# EEG_cap_v3.net
KiCad netlist of a schematic drawn in EAGLE
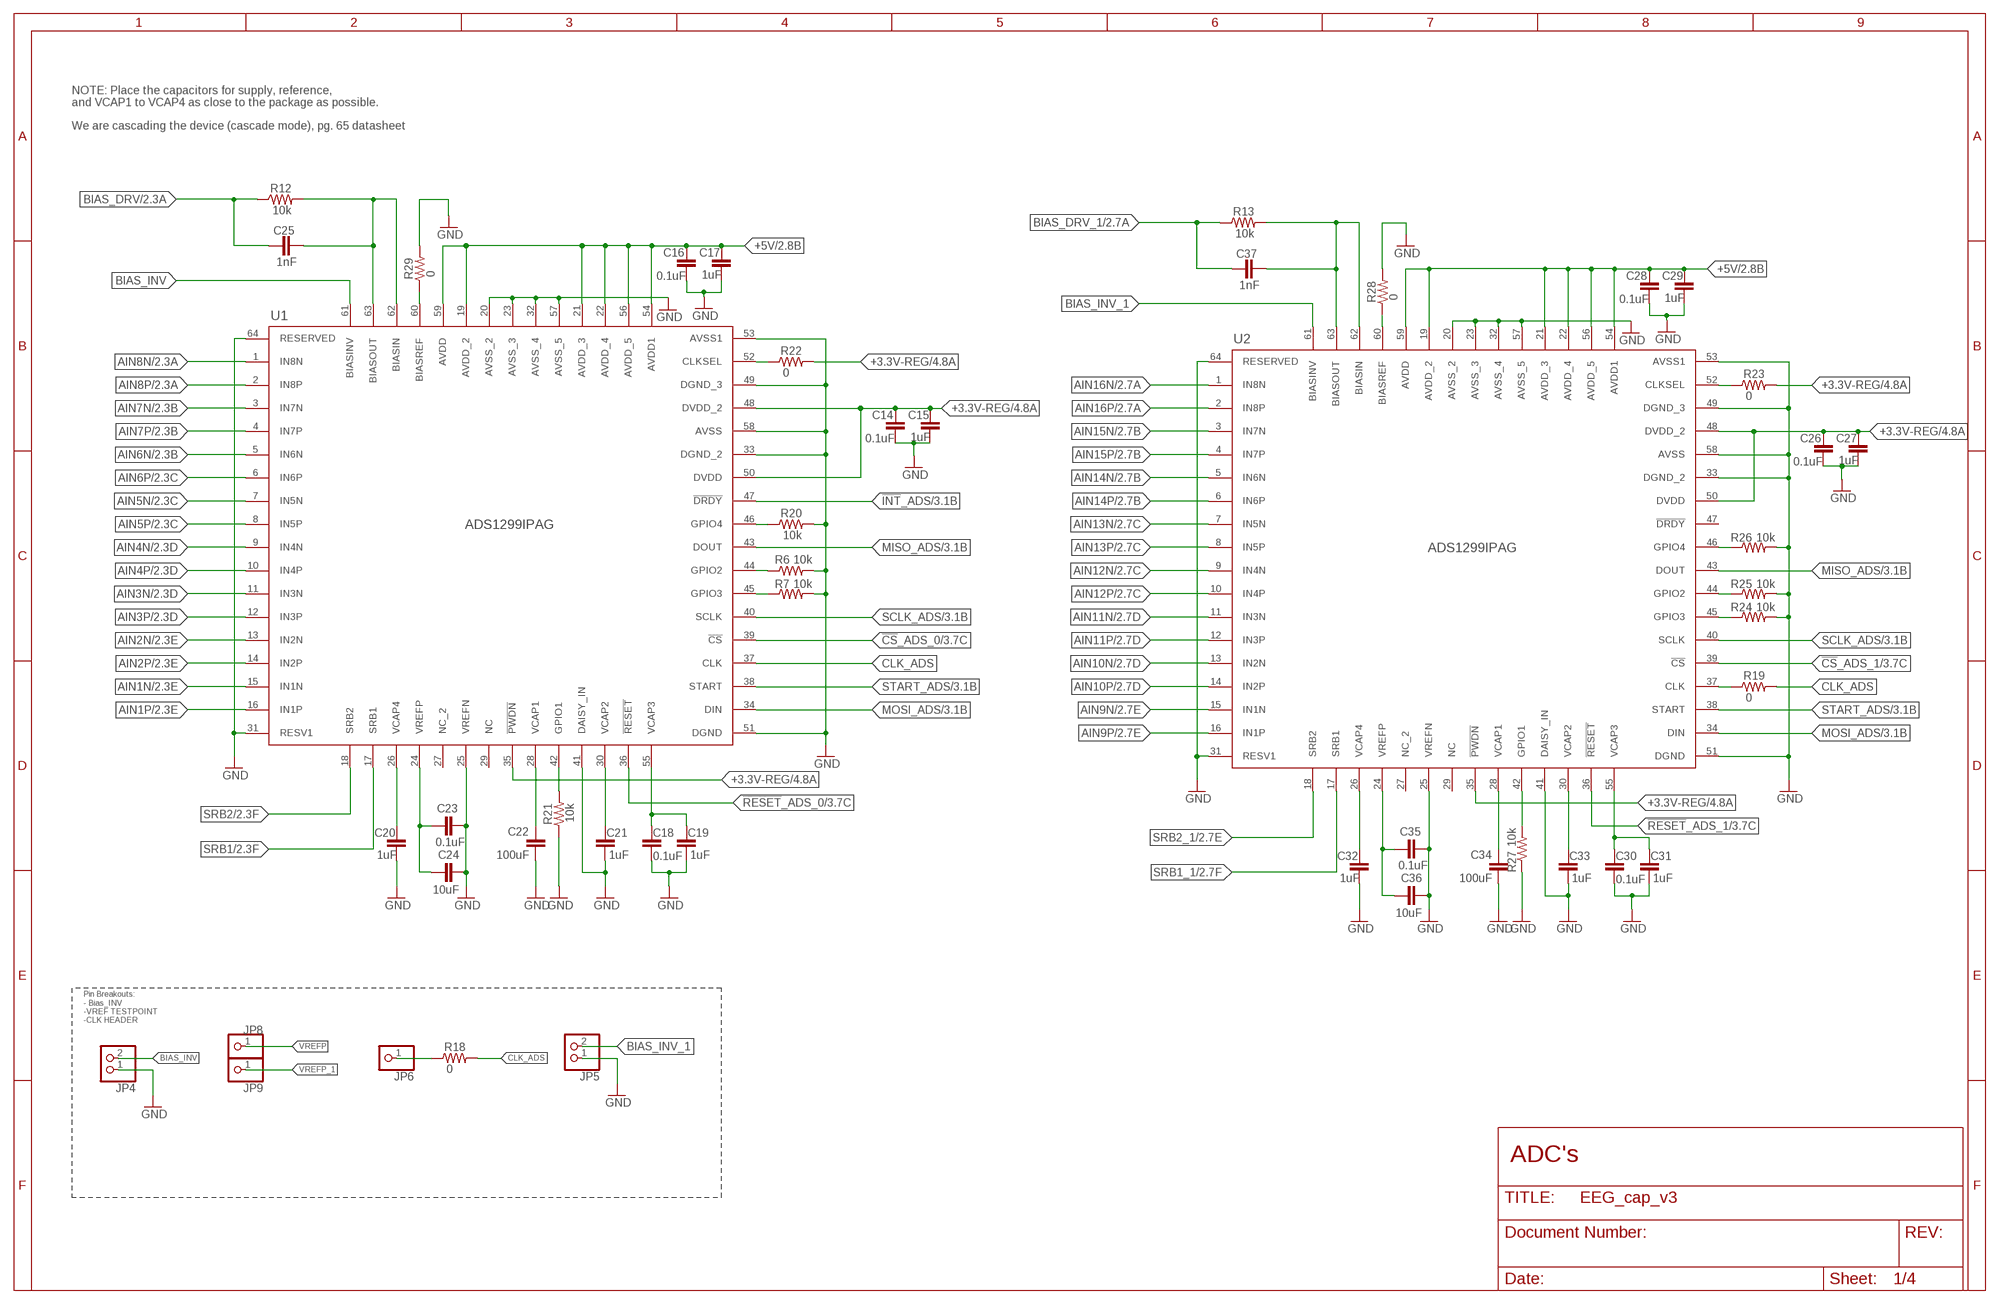
[diagram p0: schematic, sheet 1]
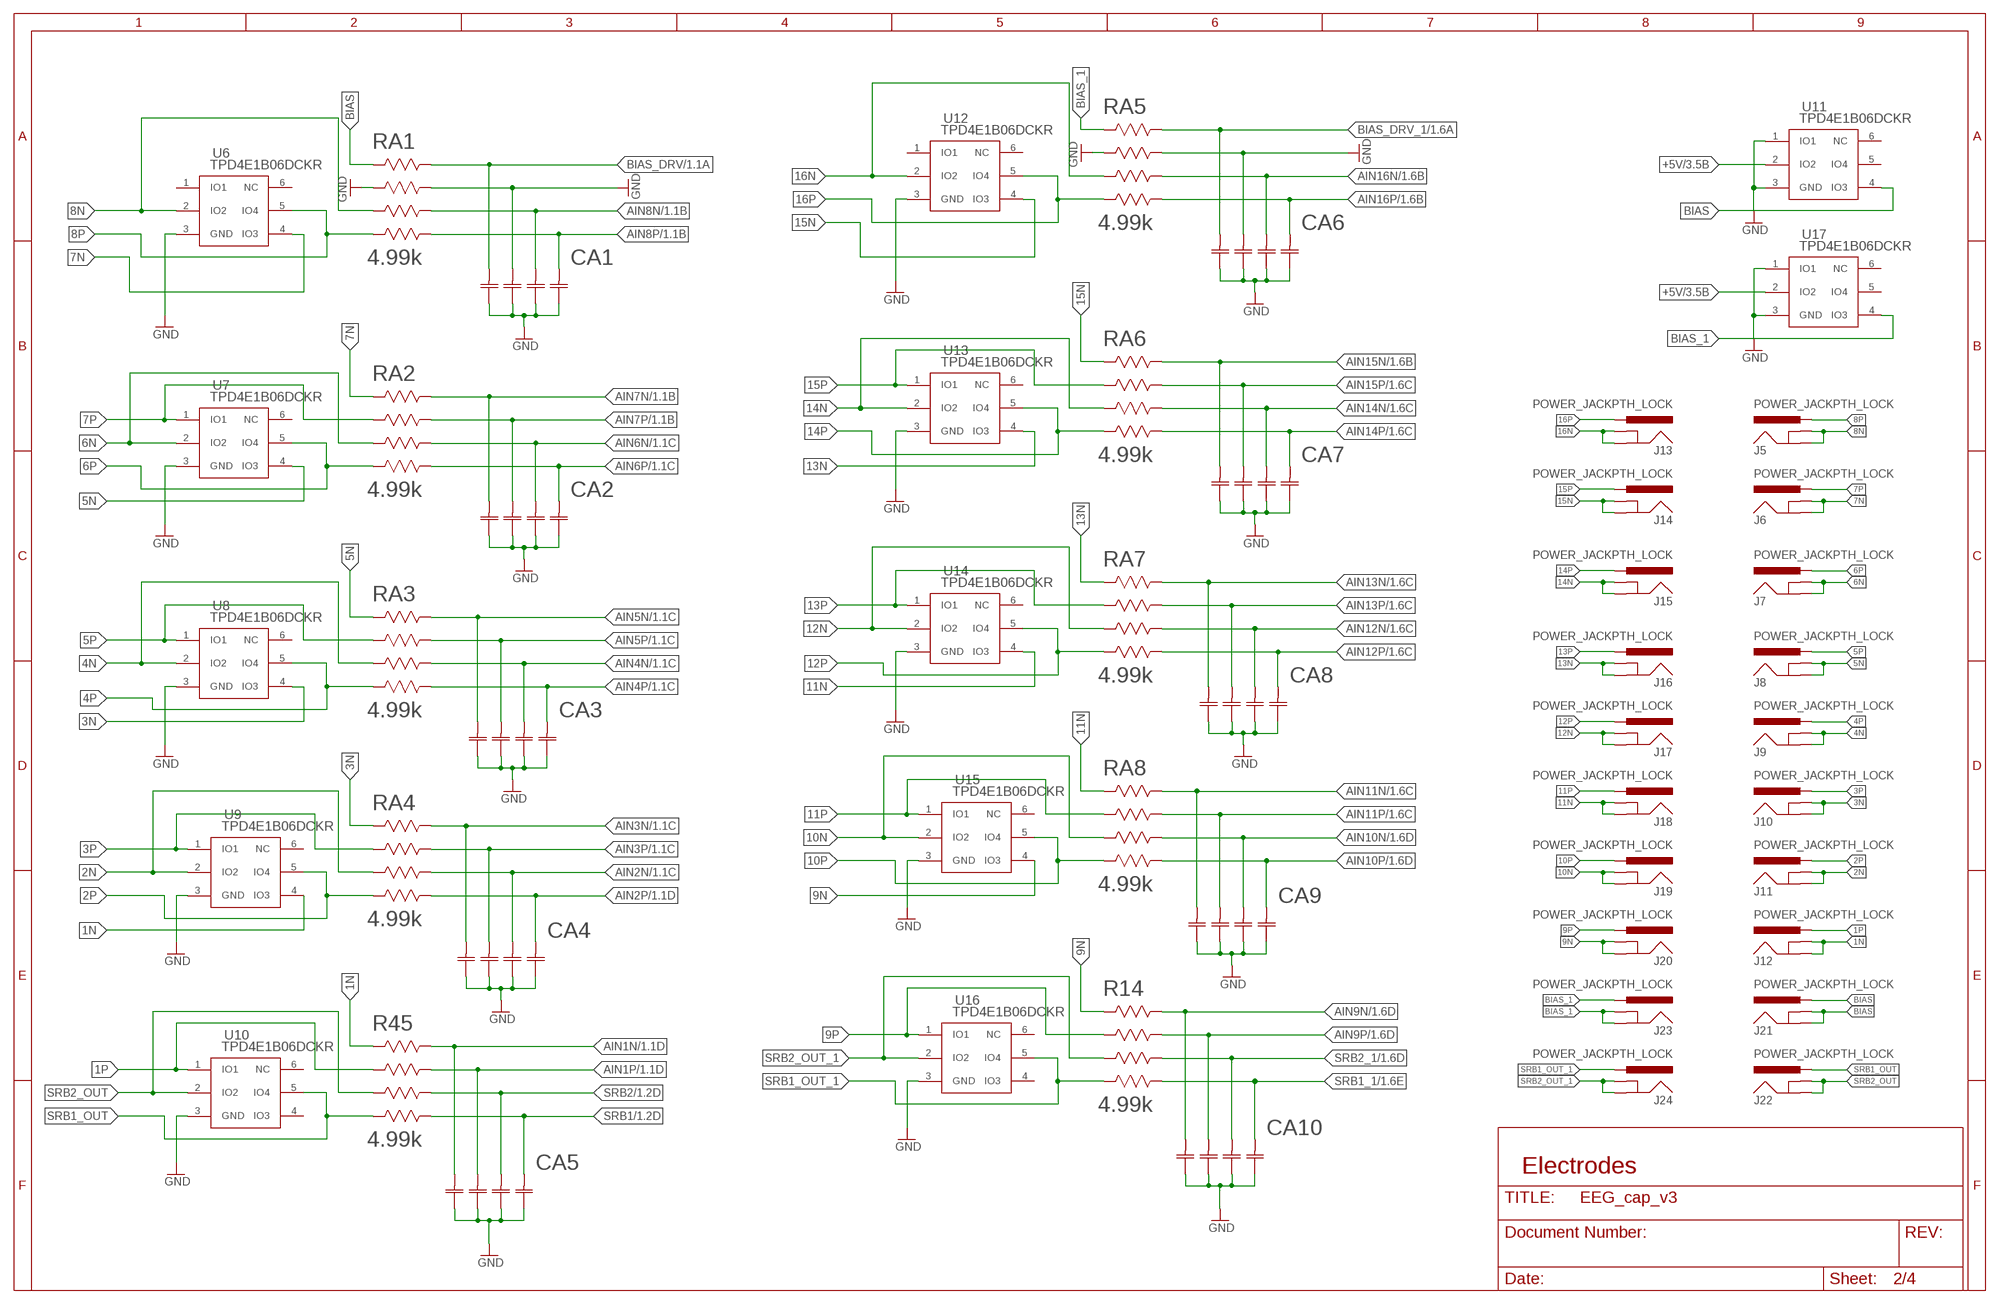
[diagram p1: schematic, sheet 2]
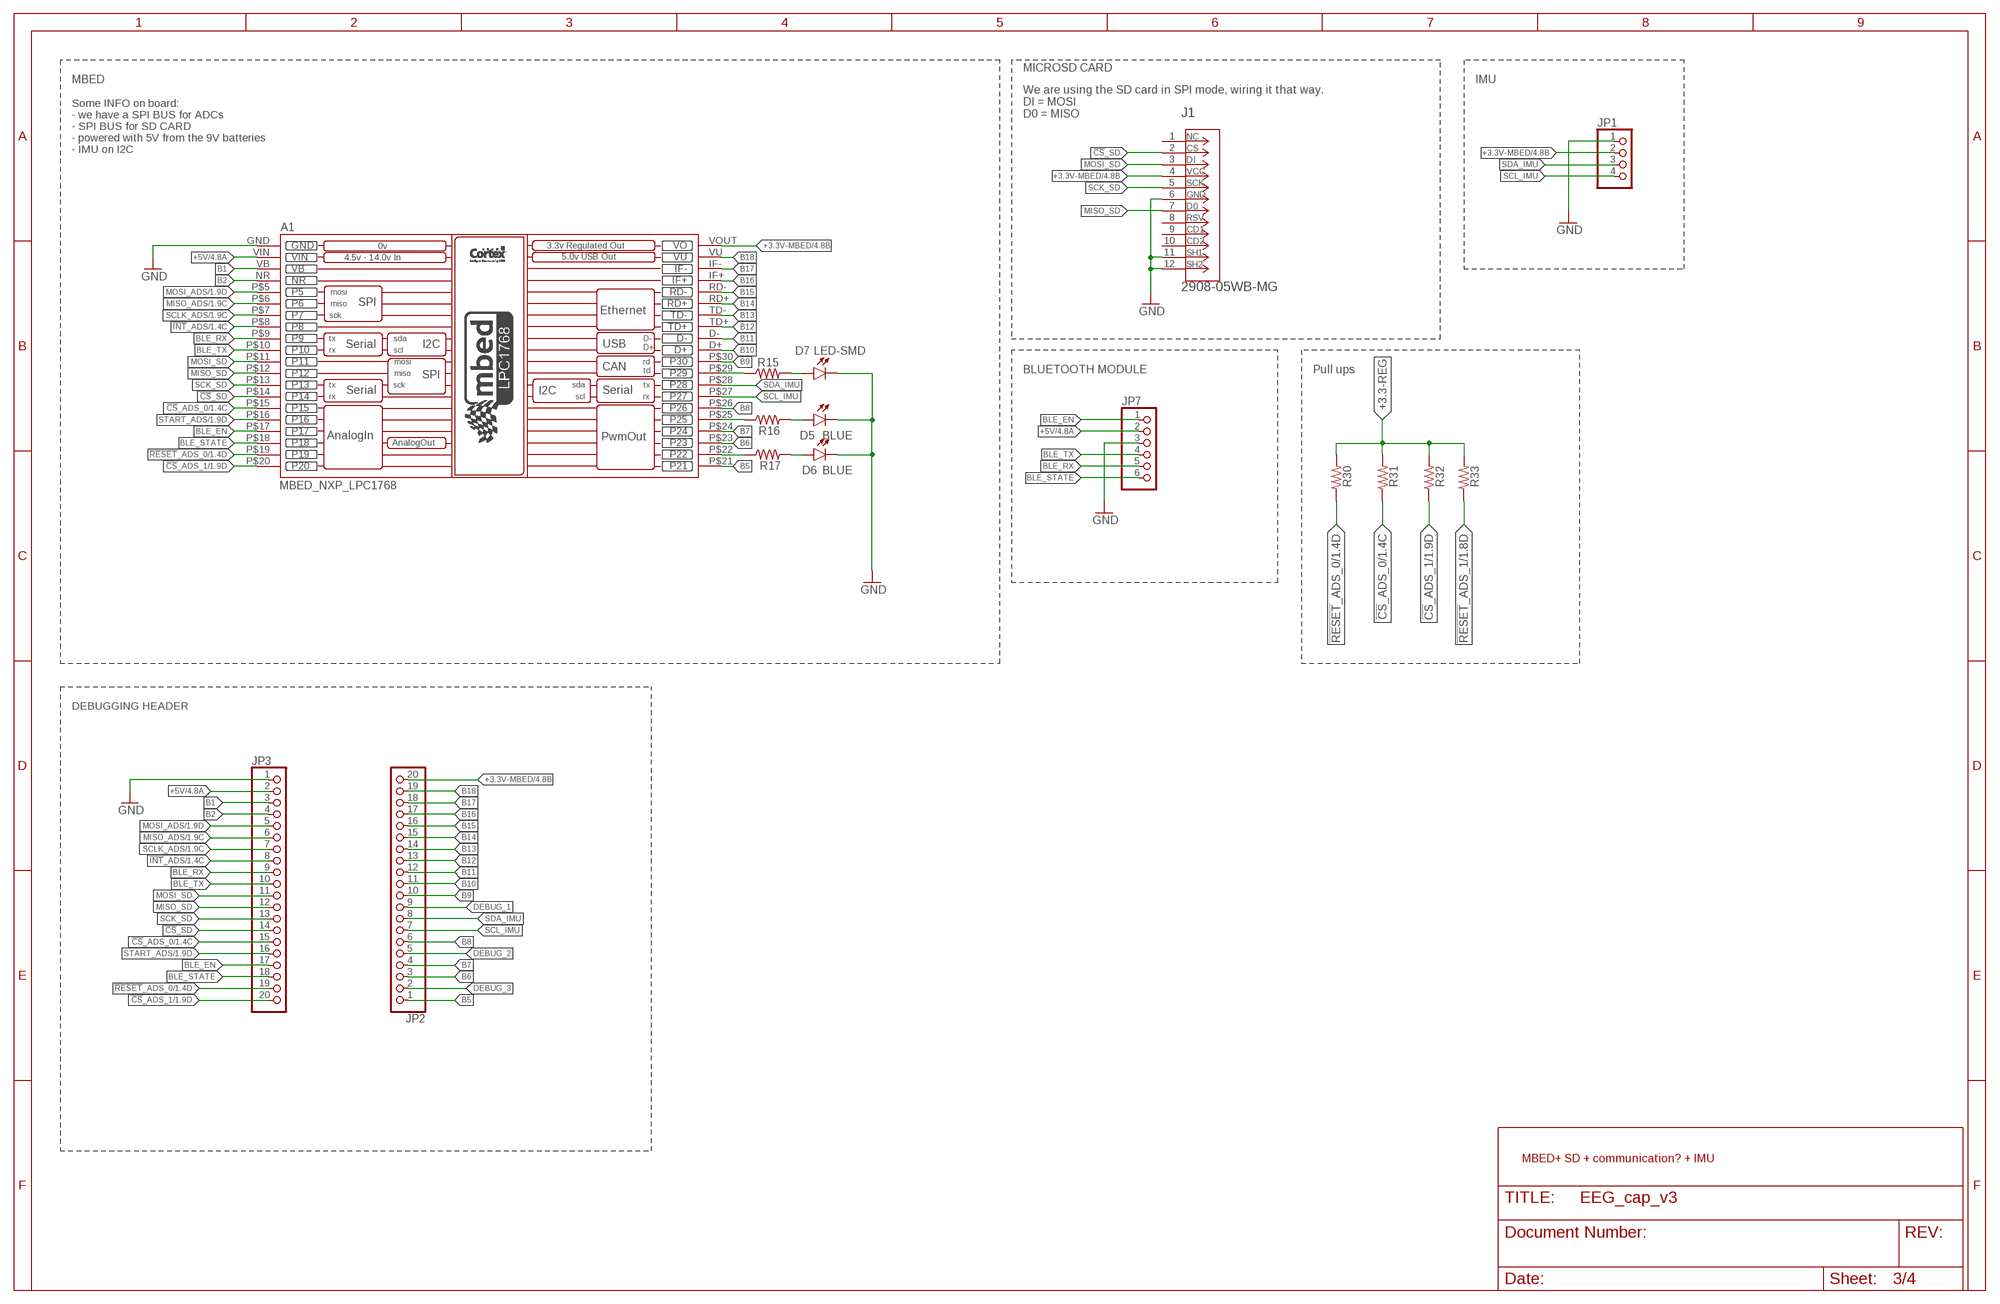
[diagram p2: schematic, sheet 3]
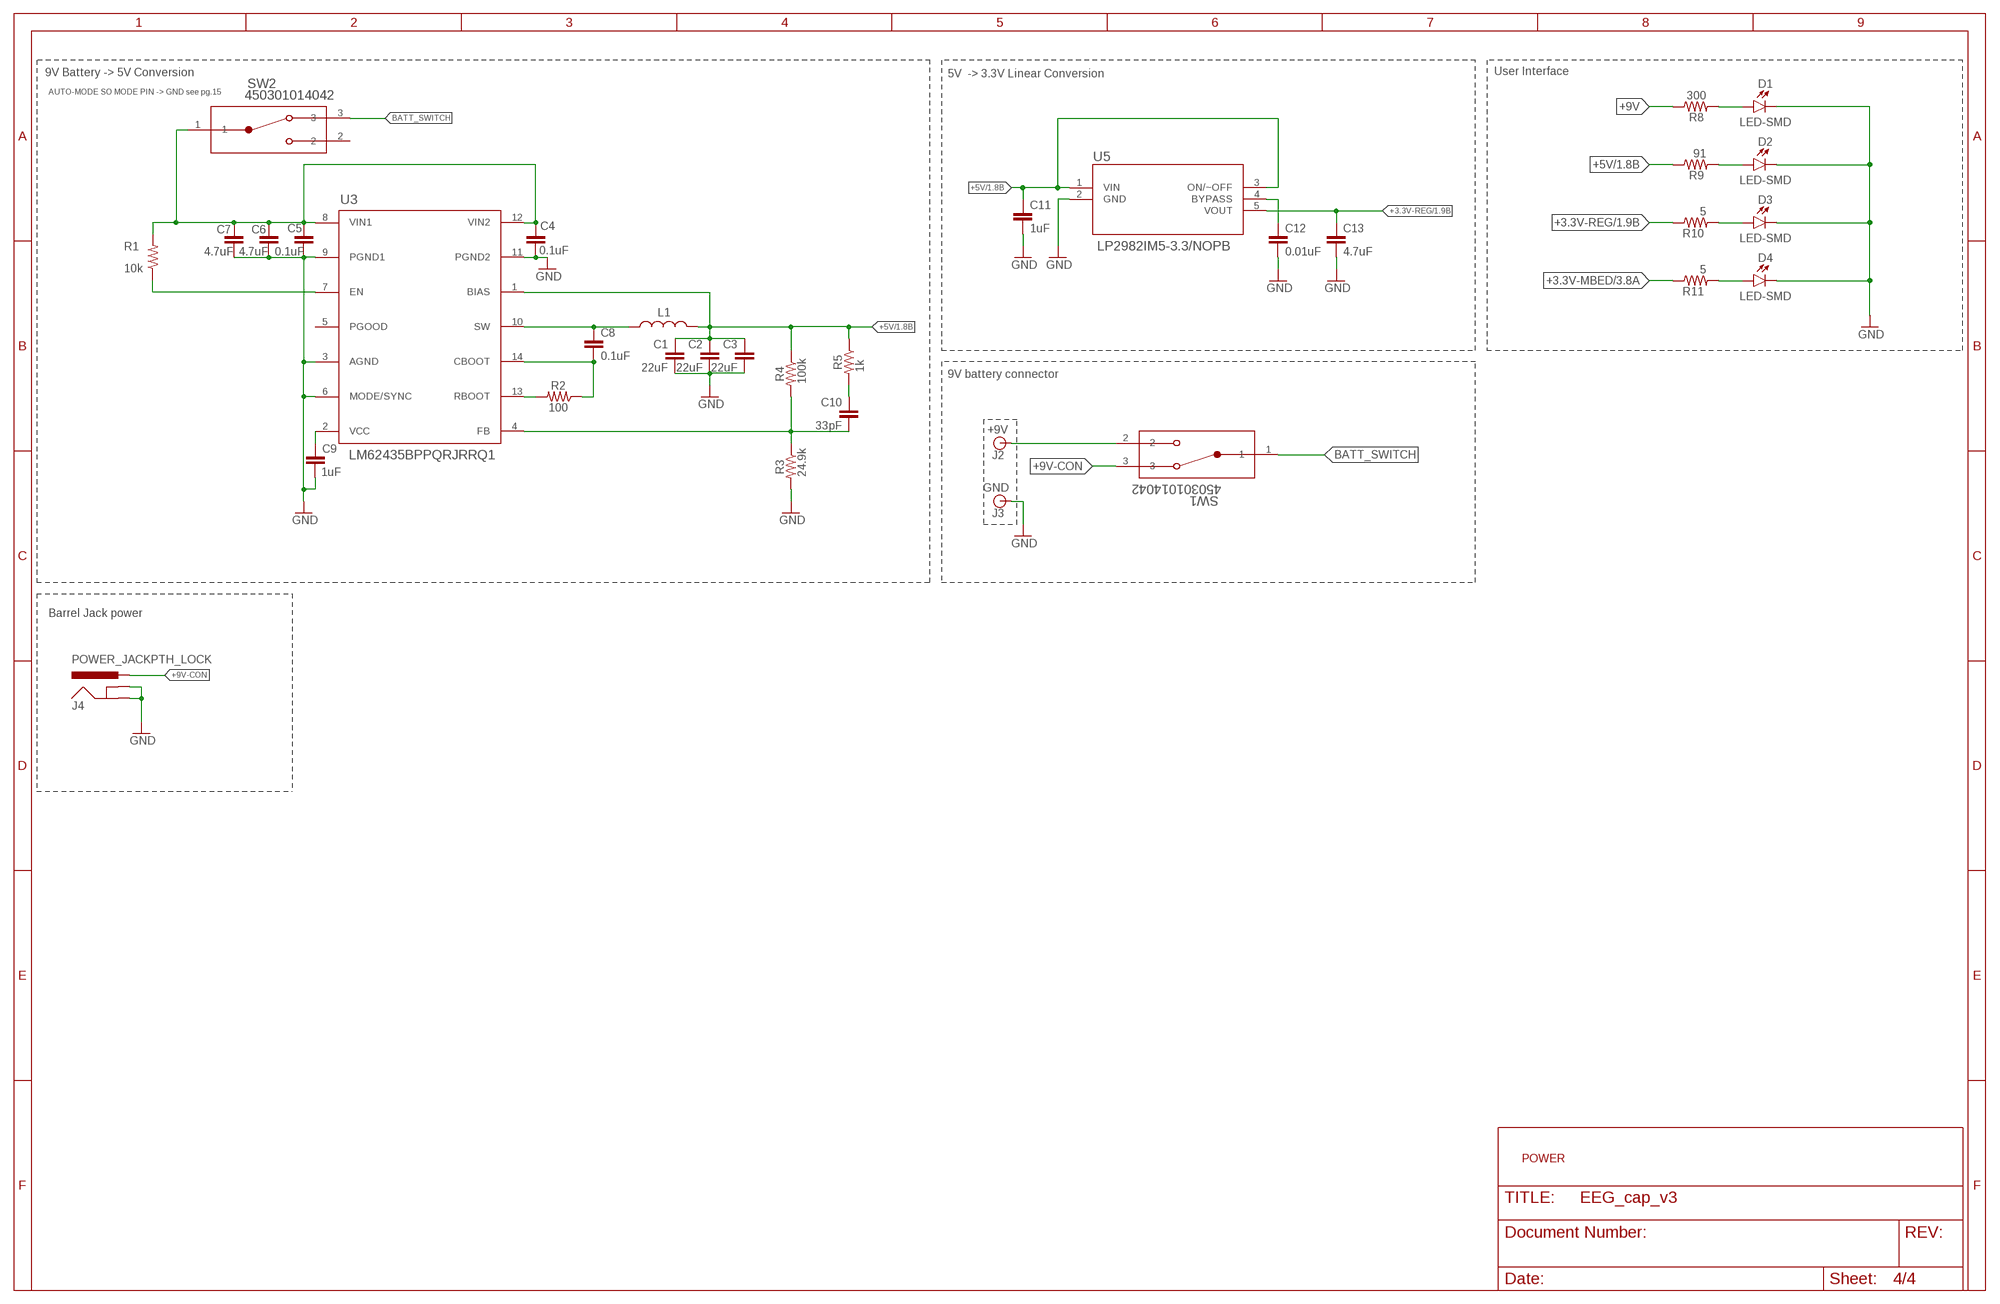
[diagram p3: schematic, sheet 4]

(export (version "E")
  (design (tool "Eeschema 10.0.6"))
  (components
    (comp (ref "C14")
      (value "0.1uF")
      (footprint "eagle-import:C0603")
      (libsource (lib "eagle-import") (part "C-EUC0603"))
    )
    (comp (ref "C15")
      (value "1uF")
      (footprint "eagle-import:C0603")
      (libsource (lib "eagle-import") (part "C-EUC0603"))
    )
    (comp (ref "C16")
      (value "0.1uF")
      (footprint "eagle-import:C0603")
      (libsource (lib "eagle-import") (part "C-EUC0603"))
    )
    (comp (ref "C17")
      (value "1uF")
      (footprint "eagle-import:C0603")
      (libsource (lib "eagle-import") (part "C-EUC0603"))
    )
    (comp (ref "C18")
      (value "0.1uF")
      (footprint "eagle-import:C0603")
      (libsource (lib "eagle-import") (part "C-EUC0603"))
    )
    (comp (ref "C19")
      (value "1uF")
      (footprint "eagle-import:C0603")
      (libsource (lib "eagle-import") (part "C-EUC0603"))
    )
    (comp (ref "C20")
      (value "1uF")
      (footprint "eagle-import:C0603")
      (libsource (lib "eagle-import") (part "C-EUC0603"))
    )
    (comp (ref "C21")
      (value "1uF")
      (footprint "eagle-import:C0603")
      (libsource (lib "eagle-import") (part "C-EUC0603"))
    )
    (comp (ref "C22")
      (value "100uF")
      (footprint "eagle-import:C1210")
      (libsource (lib "eagle-import") (part "C-EUC1210"))
    )
    (comp (ref "C23")
      (value "0.1uF")
      (footprint "eagle-import:C0603")
      (libsource (lib "eagle-import") (part "C-EUC0603"))
    )
    (comp (ref "C24")
      (value "10uF")
      (footprint "eagle-import:C0805")
      (libsource (lib "eagle-import") (part "C-EUC0805"))
    )
    (comp (ref "C25")
      (value "1nF")
      (footprint "eagle-import:C0603")
      (libsource (lib "eagle-import") (part "C-EUC0603"))
    )
    (comp (ref "C26")
      (value "0.1uF")
      (footprint "eagle-import:C0603")
      (libsource (lib "eagle-import") (part "C-EUC0603"))
    )
    (comp (ref "C27")
      (value "1uF")
      (footprint "eagle-import:C0603")
      (libsource (lib "eagle-import") (part "C-EUC0603"))
    )
    (comp (ref "C28")
      (value "0.1uF")
      (footprint "eagle-import:C0603")
      (libsource (lib "eagle-import") (part "C-EUC0603"))
    )
    (comp (ref "C29")
      (value "1uF")
      (footprint "eagle-import:C0603")
      (libsource (lib "eagle-import") (part "C-EUC0603"))
    )
    (comp (ref "C30")
      (value "0.1uF")
      (footprint "eagle-import:C0603")
      (libsource (lib "eagle-import") (part "C-EUC0603"))
    )
    (comp (ref "C31")
      (value "1uF")
      (footprint "eagle-import:C0603")
      (libsource (lib "eagle-import") (part "C-EUC0603"))
    )
    (comp (ref "C32")
      (value "1uF")
      (footprint "eagle-import:C0603")
      (libsource (lib "eagle-import") (part "C-EUC0603"))
    )
    (comp (ref "C33")
      (value "1uF")
      (footprint "eagle-import:C0603")
      (libsource (lib "eagle-import") (part "C-EUC0603"))
    )
    (comp (ref "C34")
      (value "100uF")
      (footprint "eagle-import:C1210")
      (libsource (lib "eagle-import") (part "C-EUC1210"))
    )
    (comp (ref "C35")
      (value "0.1uF")
      (footprint "eagle-import:C0603")
      (libsource (lib "eagle-import") (part "C-EUC0603"))
    )
    (comp (ref "C36")
      (value "10uF")
      (footprint "eagle-import:C0805")
      (libsource (lib "eagle-import") (part "C-EUC0805"))
    )
    (comp (ref "C37")
      (value "1nF")
      (footprint "eagle-import:C0603")
      (libsource (lib "eagle-import") (part "C-EUC0603"))
    )
    (comp (ref "JP4")
      (value "PINHD-1X2")
      (footprint "eagle-import:1X02")
      (libsource (lib "eagle-import") (part "PINHD-1X2"))
    )
    (comp (ref "JP5")
      (value "PINHD-1X2")
      (footprint "eagle-import:1X02")
      (libsource (lib "eagle-import") (part "PINHD-1X2"))
    )
    (comp (ref "JP6")
      (value "PINHD-1X1")
      (footprint "eagle-import:1X01")
      (libsource (lib "eagle-import") (part "PINHD-1X1"))
    )
    (comp (ref "JP8")
      (value "PINHD-1X1")
      (footprint "eagle-import:1X01")
      (libsource (lib "eagle-import") (part "PINHD-1X1"))
    )
    (comp (ref "JP9")
      (value "PINHD-1X1")
      (footprint "eagle-import:1X01")
      (libsource (lib "eagle-import") (part "PINHD-1X1"))
    )
    (comp (ref "R6")
      (value "10k")
      (footprint "eagle-import:R0805")
      (libsource (lib "eagle-import") (part "R-US_R0805"))
    )
    (comp (ref "R7")
      (value "10k")
      (footprint "eagle-import:R0805")
      (libsource (lib "eagle-import") (part "R-US_R0805"))
    )
    (comp (ref "R12")
      (value "10k")
      (footprint "eagle-import:R0805")
      (libsource (lib "eagle-import") (part "R-US_R0805"))
    )
    (comp (ref "R13")
      (value "10k")
      (footprint "eagle-import:R0805")
      (libsource (lib "eagle-import") (part "R-US_R0805"))
    )
    (comp (ref "R18")
      (value "0")
      (footprint "eagle-import:R0805")
      (libsource (lib "eagle-import") (part "R-US_R0805"))
    )
    (comp (ref "R19")
      (value "0")
      (footprint "eagle-import:R0805")
      (libsource (lib "eagle-import") (part "R-US_R0805"))
    )
    (comp (ref "R20")
      (value "10k")
      (footprint "eagle-import:R0805")
      (libsource (lib "eagle-import") (part "R-US_R0805"))
    )
    (comp (ref "R21")
      (value "10k")
      (footprint "eagle-import:R0805")
      (libsource (lib "eagle-import") (part "R-US_R0805"))
    )
    (comp (ref "R22")
      (value "0")
      (footprint "eagle-import:R0805")
      (libsource (lib "eagle-import") (part "R-US_R0805"))
    )
    (comp (ref "R23")
      (value "0")
      (footprint "eagle-import:R0805")
      (libsource (lib "eagle-import") (part "R-US_R0805"))
    )
    (comp (ref "R24")
      (value "10k")
      (footprint "eagle-import:R0805")
      (libsource (lib "eagle-import") (part "R-US_R0805"))
    )
    (comp (ref "R25")
      (value "10k")
      (footprint "eagle-import:R0805")
      (libsource (lib "eagle-import") (part "R-US_R0805"))
    )
    (comp (ref "R26")
      (value "10k")
      (footprint "eagle-import:R0805")
      (libsource (lib "eagle-import") (part "R-US_R0805"))
    )
    (comp (ref "R27")
      (value "10k")
      (footprint "eagle-import:R0805")
      (libsource (lib "eagle-import") (part "R-US_R0805"))
    )
    (comp (ref "R28")
      (value "0")
      (footprint "eagle-import:R0805")
      (libsource (lib "eagle-import") (part "R-US_R0805"))
    )
    (comp (ref "R29")
      (value "0")
      (footprint "eagle-import:R0805")
      (libsource (lib "eagle-import") (part "R-US_R0805"))
    )
    (comp (ref "U1")
      (value "ADS1299IPAG")
      (footprint "eagle-import:PAG64_TEX")
      (fields (field (name "COPYRIGHT") "Copyright (C) 2021 Ultra Librarian. All rights reserved."))
      (libsource (lib "eagle-import") (part "ADS1299IPAG"))
    )
    (comp (ref "U2")
      (value "ADS1299IPAG")
      (footprint "eagle-import:PAG64_TEX")
      (fields (field (name "COPYRIGHT") "Copyright (C) 2021 Ultra Librarian. All rights reserved."))
      (libsource (lib "eagle-import") (part "ADS1299IPAG"))
    )
    (comp (ref "CA1")
      (value "4.7nF")
      (footprint "eagle-import:CAP_CA0612_3P2X1P6_YAG")
      (libsource (lib "eagle-import") (part "CAP_ARRAY"))
    )
    (comp (ref "CA2")
      (value "4.7nF")
      (footprint "eagle-import:CAP_CA0612_3P2X1P6_YAG")
      (libsource (lib "eagle-import") (part "CAP_ARRAY"))
    )
    (comp (ref "CA3")
      (value "4.7nF")
      (footprint "eagle-import:CAP_CA0612_3P2X1P6_YAG")
      (libsource (lib "eagle-import") (part "CAP_ARRAY"))
    )
    (comp (ref "CA4")
      (value "4.7nF")
      (footprint "eagle-import:CAP_CA0612_3P2X1P6_YAG")
      (libsource (lib "eagle-import") (part "CAP_ARRAY"))
    )
    (comp (ref "CA5")
      (value "4.7nF")
      (footprint "eagle-import:CAP_CA0612_3P2X1P6_YAG")
      (libsource (lib "eagle-import") (part "CAP_ARRAY"))
    )
    (comp (ref "CA6")
      (value "4.7nF")
      (footprint "eagle-import:CAP_CA0612_3P2X1P6_YAG")
      (libsource (lib "eagle-import") (part "CAP_ARRAY"))
    )
    (comp (ref "CA7")
      (value "4.7nF")
      (footprint "eagle-import:CAP_CA0612_3P2X1P6_YAG")
      (libsource (lib "eagle-import") (part "CAP_ARRAY"))
    )
    (comp (ref "CA8")
      (value "4.7nF")
      (footprint "eagle-import:CAP_CA0612_3P2X1P6_YAG")
      (libsource (lib "eagle-import") (part "CAP_ARRAY"))
    )
    (comp (ref "CA9")
      (value "4.7nF")
      (footprint "eagle-import:CAP_CA0612_3P2X1P6_YAG")
      (libsource (lib "eagle-import") (part "CAP_ARRAY"))
    )
    (comp (ref "CA10")
      (value "4.7nF")
      (footprint "eagle-import:CAP_CA0612_3P2X1P6_YAG")
      (libsource (lib "eagle-import") (part "CAP_ARRAY"))
    )
    (comp (ref "J5")
      (value "POWER_JACKPTH_LOCK")
      (footprint "eagle-import:POWER_JACK_PTH_LOCK")
      (libsource (lib "eagle-import") (part "POWER_JACKPTH_LOCK"))
    )
    (comp (ref "J6")
      (value "POWER_JACKPTH_LOCK")
      (footprint "eagle-import:POWER_JACK_PTH_LOCK")
      (libsource (lib "eagle-import") (part "POWER_JACKPTH_LOCK"))
    )
    (comp (ref "J7")
      (value "POWER_JACKPTH_LOCK")
      (footprint "eagle-import:POWER_JACK_PTH_LOCK")
      (libsource (lib "eagle-import") (part "POWER_JACKPTH_LOCK"))
    )
    (comp (ref "J8")
      (value "POWER_JACKPTH_LOCK")
      (footprint "eagle-import:POWER_JACK_PTH_LOCK")
      (libsource (lib "eagle-import") (part "POWER_JACKPTH_LOCK"))
    )
    (comp (ref "J9")
      (value "POWER_JACKPTH_LOCK")
      (footprint "eagle-import:POWER_JACK_PTH_LOCK")
      (libsource (lib "eagle-import") (part "POWER_JACKPTH_LOCK"))
    )
    (comp (ref "J10")
      (value "POWER_JACKPTH_LOCK")
      (footprint "eagle-import:POWER_JACK_PTH_LOCK")
      (libsource (lib "eagle-import") (part "POWER_JACKPTH_LOCK"))
    )
    (comp (ref "J11")
      (value "POWER_JACKPTH_LOCK")
      (footprint "eagle-import:POWER_JACK_PTH_LOCK")
      (libsource (lib "eagle-import") (part "POWER_JACKPTH_LOCK"))
    )
    (comp (ref "J12")
      (value "POWER_JACKPTH_LOCK")
      (footprint "eagle-import:POWER_JACK_PTH_LOCK")
      (libsource (lib "eagle-import") (part "POWER_JACKPTH_LOCK"))
    )
    (comp (ref "J13")
      (value "POWER_JACKPTH_LOCK")
      (footprint "eagle-import:POWER_JACK_PTH_LOCK")
      (libsource (lib "eagle-import") (part "POWER_JACKPTH_LOCK"))
    )
    (comp (ref "J14")
      (value "POWER_JACKPTH_LOCK")
      (footprint "eagle-import:POWER_JACK_PTH_LOCK")
      (libsource (lib "eagle-import") (part "POWER_JACKPTH_LOCK"))
    )
    (comp (ref "J15")
      (value "POWER_JACKPTH_LOCK")
      (footprint "eagle-import:POWER_JACK_PTH_LOCK")
      (libsource (lib "eagle-import") (part "POWER_JACKPTH_LOCK"))
    )
    (comp (ref "J16")
      (value "POWER_JACKPTH_LOCK")
      (footprint "eagle-import:POWER_JACK_PTH_LOCK")
      (libsource (lib "eagle-import") (part "POWER_JACKPTH_LOCK"))
    )
    (comp (ref "J17")
      (value "POWER_JACKPTH_LOCK")
      (footprint "eagle-import:POWER_JACK_PTH_LOCK")
      (libsource (lib "eagle-import") (part "POWER_JACKPTH_LOCK"))
    )
    (comp (ref "J18")
      (value "POWER_JACKPTH_LOCK")
      (footprint "eagle-import:POWER_JACK_PTH_LOCK")
      (libsource (lib "eagle-import") (part "POWER_JACKPTH_LOCK"))
    )
    (comp (ref "J19")
      (value "POWER_JACKPTH_LOCK")
      (footprint "eagle-import:POWER_JACK_PTH_LOCK")
      (libsource (lib "eagle-import") (part "POWER_JACKPTH_LOCK"))
    )
    (comp (ref "J20")
      (value "POWER_JACKPTH_LOCK")
      (footprint "eagle-import:POWER_JACK_PTH_LOCK")
      (libsource (lib "eagle-import") (part "POWER_JACKPTH_LOCK"))
    )
    (comp (ref "J21")
      (value "POWER_JACKPTH_LOCK")
      (footprint "eagle-import:POWER_JACK_PTH_LOCK")
      (libsource (lib "eagle-import") (part "POWER_JACKPTH_LOCK"))
    )
    (comp (ref "J22")
      (value "POWER_JACKPTH_LOCK")
      (footprint "eagle-import:POWER_JACK_PTH_LOCK")
      (libsource (lib "eagle-import") (part "POWER_JACKPTH_LOCK"))
    )
    (comp (ref "J23")
      (value "POWER_JACKPTH_LOCK")
      (footprint "eagle-import:POWER_JACK_PTH_LOCK")
      (libsource (lib "eagle-import") (part "POWER_JACKPTH_LOCK"))
    )
    (comp (ref "J24")
      (value "POWER_JACKPTH_LOCK")
      (footprint "eagle-import:POWER_JACK_PTH_LOCK")
      (libsource (lib "eagle-import") (part "POWER_JACKPTH_LOCK"))
    )
    (comp (ref "R14")
      (value "4.99k")
      (footprint "eagle-import:BO_CAT16")
      (fields
        (field (name "MANUFACTURER_PART_NUMBER") "CAT16-220J4LF")
        (field (name "COPYRIGHT") "Copyright (C) 2021 Ultra Librarian. All rights reserved.")
      )
      (libsource (lib "eagle-import") (part "CAT16-220J4LF"))
    )
    (comp (ref "R45")
      (value "4.99k")
      (footprint "eagle-import:BO_CAT16")
      (fields
        (field (name "MANUFACTURER_PART_NUMBER") "CAT16-220J4LF")
        (field (name "COPYRIGHT") "Copyright (C) 2021 Ultra Librarian. All rights reserved.")
      )
      (libsource (lib "eagle-import") (part "CAT16-220J4LF"))
    )
    (comp (ref "RA1")
      (value "4.99k")
      (footprint "eagle-import:BO_CAT16")
      (fields
        (field (name "MANUFACTURER_PART_NUMBER") "CAT16-220J4LF")
        (field (name "COPYRIGHT") "Copyright (C) 2021 Ultra Librarian. All rights reserved.")
      )
      (libsource (lib "eagle-import") (part "CAT16-220J4LF"))
    )
    (comp (ref "RA2")
      (value "4.99k")
      (footprint "eagle-import:BO_CAT16")
      (fields
        (field (name "MANUFACTURER_PART_NUMBER") "CAT16-220J4LF")
        (field (name "COPYRIGHT") "Copyright (C) 2021 Ultra Librarian. All rights reserved.")
      )
      (libsource (lib "eagle-import") (part "CAT16-220J4LF"))
    )
    (comp (ref "RA3")
      (value "4.99k")
      (footprint "eagle-import:BO_CAT16")
      (fields
        (field (name "MANUFACTURER_PART_NUMBER") "CAT16-220J4LF")
        (field (name "COPYRIGHT") "Copyright (C) 2021 Ultra Librarian. All rights reserved.")
      )
      (libsource (lib "eagle-import") (part "CAT16-220J4LF"))
    )
    (comp (ref "RA4")
      (value "4.99k")
      (footprint "eagle-import:BO_CAT16")
      (fields
        (field (name "MANUFACTURER_PART_NUMBER") "CAT16-220J4LF")
        (field (name "COPYRIGHT") "Copyright (C) 2021 Ultra Librarian. All rights reserved.")
      )
      (libsource (lib "eagle-import") (part "CAT16-220J4LF"))
    )
    (comp (ref "RA5")
      (value "4.99k")
      (footprint "eagle-import:BO_CAT16")
      (fields
        (field (name "MANUFACTURER_PART_NUMBER") "CAT16-220J4LF")
        (field (name "COPYRIGHT") "Copyright (C) 2021 Ultra Librarian. All rights reserved.")
      )
      (libsource (lib "eagle-import") (part "CAT16-220J4LF"))
    )
    (comp (ref "RA6")
      (value "4.99k")
      (footprint "eagle-import:BO_CAT16")
      (fields
        (field (name "MANUFACTURER_PART_NUMBER") "CAT16-220J4LF")
        (field (name "COPYRIGHT") "Copyright (C) 2021 Ultra Librarian. All rights reserved.")
      )
      (libsource (lib "eagle-import") (part "CAT16-220J4LF"))
    )
    (comp (ref "RA7")
      (value "4.99k")
      (footprint "eagle-import:BO_CAT16")
      (fields
        (field (name "MANUFACTURER_PART_NUMBER") "CAT16-220J4LF")
        (field (name "COPYRIGHT") "Copyright (C) 2021 Ultra Librarian. All rights reserved.")
      )
      (libsource (lib "eagle-import") (part "CAT16-220J4LF"))
    )
    (comp (ref "RA8")
      (value "4.99k")
      (footprint "eagle-import:BO_CAT16")
      (fields
        (field (name "MANUFACTURER_PART_NUMBER") "CAT16-220J4LF")
        (field (name "COPYRIGHT") "Copyright (C) 2021 Ultra Librarian. All rights reserved.")
      )
      (libsource (lib "eagle-import") (part "CAT16-220J4LF"))
    )
    (comp (ref "U6")
      (value "TPD4E1B06DCKR")
      (footprint "eagle-import:DCK6_TEX")
      (fields (field (name "COPYRIGHT") "Copyright (C) 2021 Ultra Librarian. All rights reserved."))
      (libsource (lib "eagle-import") (part "TPD4E1B06DCKR"))
    )
    (comp (ref "U7")
      (value "TPD4E1B06DCKR")
      (footprint "eagle-import:DCK6_TEX")
      (fields (field (name "COPYRIGHT") "Copyright (C) 2021 Ultra Librarian. All rights reserved."))
      (libsource (lib "eagle-import") (part "TPD4E1B06DCKR"))
    )
    (comp (ref "U8")
      (value "TPD4E1B06DCKR")
      (footprint "eagle-import:DCK6_TEX")
      (fields (field (name "COPYRIGHT") "Copyright (C) 2021 Ultra Librarian. All rights reserved."))
      (libsource (lib "eagle-import") (part "TPD4E1B06DCKR"))
    )
    (comp (ref "U9")
      (value "TPD4E1B06DCKR")
      (footprint "eagle-import:DCK6_TEX")
      (fields (field (name "COPYRIGHT") "Copyright (C) 2021 Ultra Librarian. All rights reserved."))
      (libsource (lib "eagle-import") (part "TPD4E1B06DCKR"))
    )
    (comp (ref "U10")
      (value "TPD4E1B06DCKR")
      (footprint "eagle-import:DCK6_TEX")
      (fields (field (name "COPYRIGHT") "Copyright (C) 2021 Ultra Librarian. All rights reserved."))
      (libsource (lib "eagle-import") (part "TPD4E1B06DCKR"))
    )
    (comp (ref "U11")
      (value "TPD4E1B06DCKR")
      (footprint "eagle-import:DCK6_TEX")
      (fields (field (name "COPYRIGHT") "Copyright (C) 2021 Ultra Librarian. All rights reserved."))
      (libsource (lib "eagle-import") (part "TPD4E1B06DCKR"))
    )
    (comp (ref "U12")
      (value "TPD4E1B06DCKR")
      (footprint "eagle-import:DCK6_TEX")
      (fields (field (name "COPYRIGHT") "Copyright (C) 2021 Ultra Librarian. All rights reserved."))
      (libsource (lib "eagle-import") (part "TPD4E1B06DCKR"))
    )
    (comp (ref "U13")
      (value "TPD4E1B06DCKR")
      (footprint "eagle-import:DCK6_TEX")
      (fields (field (name "COPYRIGHT") "Copyright (C) 2021 Ultra Librarian. All rights reserved."))
      (libsource (lib "eagle-import") (part "TPD4E1B06DCKR"))
    )
    (comp (ref "U14")
      (value "TPD4E1B06DCKR")
      (footprint "eagle-import:DCK6_TEX")
      (fields (field (name "COPYRIGHT") "Copyright (C) 2021 Ultra Librarian. All rights reserved."))
      (libsource (lib "eagle-import") (part "TPD4E1B06DCKR"))
    )
    (comp (ref "U15")
      (value "TPD4E1B06DCKR")
      (footprint "eagle-import:DCK6_TEX")
      (fields (field (name "COPYRIGHT") "Copyright (C) 2021 Ultra Librarian. All rights reserved."))
      (libsource (lib "eagle-import") (part "TPD4E1B06DCKR"))
    )
    (comp (ref "U16")
      (value "TPD4E1B06DCKR")
      (footprint "eagle-import:DCK6_TEX")
      (fields (field (name "COPYRIGHT") "Copyright (C) 2021 Ultra Librarian. All rights reserved."))
      (libsource (lib "eagle-import") (part "TPD4E1B06DCKR"))
    )
    (comp (ref "U17")
      (value "TPD4E1B06DCKR")
      (footprint "eagle-import:DCK6_TEX")
      (fields (field (name "COPYRIGHT") "Copyright (C) 2021 Ultra Librarian. All rights reserved."))
      (libsource (lib "eagle-import") (part "TPD4E1B06DCKR"))
    )
    (comp (ref "C1")
      (value "22uF")
      (footprint "eagle-import:C0805")
      (libsource (lib "eagle-import") (part "C-EUC0805"))
    )
    (comp (ref "C2")
      (value "22uF")
      (footprint "eagle-import:C0805")
      (libsource (lib "eagle-import") (part "C-EUC0805"))
    )
    (comp (ref "C3")
      (value "22uF")
      (footprint "eagle-import:C0805")
      (libsource (lib "eagle-import") (part "C-EUC0805"))
    )
    (comp (ref "C4")
      (value "0.1uF")
      (footprint "eagle-import:C0805")
      (libsource (lib "eagle-import") (part "C-EUC0805"))
    )
    (comp (ref "C5")
      (value "0.1uF")
      (footprint "eagle-import:C0805")
      (libsource (lib "eagle-import") (part "C-EUC0805"))
    )
    (comp (ref "C6")
      (value "4.7uF")
      (footprint "eagle-import:C0805")
      (libsource (lib "eagle-import") (part "C-EUC0805"))
    )
    (comp (ref "C7")
      (value "4.7uF")
      (footprint "eagle-import:C0805")
      (libsource (lib "eagle-import") (part "C-EUC0805"))
    )
    (comp (ref "C8")
      (value "0.1uF")
      (footprint "eagle-import:C0805")
      (libsource (lib "eagle-import") (part "C-EUC0805"))
    )
    (comp (ref "C9")
      (value "1uF")
      (footprint "eagle-import:C0805")
      (libsource (lib "eagle-import") (part "C-EUC0805"))
    )
    (comp (ref "C10")
      (value "33pF")
      (footprint "eagle-import:C0805")
      (libsource (lib "eagle-import") (part "C-EUC0805"))
    )
    (comp (ref "C11")
      (value "1uF")
      (footprint "eagle-import:C0805")
      (libsource (lib "eagle-import") (part "C-EUC0805"))
    )
    (comp (ref "C12")
      (value "0.01uF")
      (footprint "eagle-import:C0805")
      (libsource (lib "eagle-import") (part "C-EUC0805"))
    )
    (comp (ref "C13")
      (value "4.7uF")
      (footprint "eagle-import:C0805")
      (libsource (lib "eagle-import") (part "C-EUC0805"))
    )
    (comp (ref "D1")
      (value "LED-SMD")
      (footprint "eagle-import:LED0603")
      (libsource (lib "eagle-import") (part "LED-SMD"))
    )
    (comp (ref "D2")
      (value "LED-SMD")
      (footprint "eagle-import:LED0603")
      (libsource (lib "eagle-import") (part "LED-SMD"))
    )
    (comp (ref "D3")
      (value "LED-SMD")
      (footprint "eagle-import:LED0603")
      (libsource (lib "eagle-import") (part "LED-SMD"))
    )
    (comp (ref "D4")
      (value "LED-SMD")
      (footprint "eagle-import:LED0603")
      (libsource (lib "eagle-import") (part "LED-SMD"))
    )
    (comp (ref "J2")
      (value "+9V")
      (footprint "eagle-import:BANANA_CONN")
      (libsource (lib "eagle-import") (part "BANANA_CONN"))
    )
    (comp (ref "J3")
      (value "GND")
      (footprint "eagle-import:BANANA_CONN")
      (libsource (lib "eagle-import") (part "BANANA_CONN"))
    )
    (comp (ref "J4")
      (value "POWER_JACKPTH_LOCK")
      (footprint "eagle-import:POWER_JACK_PTH_LOCK")
      (libsource (lib "eagle-import") (part "POWER_JACKPTH_LOCK"))
    )
    (comp (ref "L1")
      (value "DFE252010P-1R5M=P2")
      (footprint "eagle-import:INDC2520X100N")
      (fields (field (name "DIGI-KEY_PART_NUMBER") "490-10636-1-ND") (field (name "MF") "Murata"))
      (libsource (lib "eagle-import") (part "DFE252010P-1R5M=P2"))
    )
    (comp (ref "R1")
      (value "10k")
      (footprint "eagle-import:R0805")
      (libsource (lib "eagle-import") (part "R-US_R0805"))
    )
    (comp (ref "R2")
      (value "100")
      (footprint "eagle-import:R0805")
      (libsource (lib "eagle-import") (part "R-US_R0805"))
    )
    (comp (ref "R3")
      (value "24.9k")
      (footprint "eagle-import:R0805")
      (libsource (lib "eagle-import") (part "R-US_R0805"))
    )
    (comp (ref "R4")
      (value "100k")
      (footprint "eagle-import:R0805")
      (libsource (lib "eagle-import") (part "R-US_R0805"))
    )
    (comp (ref "R5")
      (value "1k")
      (footprint "eagle-import:R0805")
      (libsource (lib "eagle-import") (part "R-US_R0805"))
    )
    (comp (ref "R8")
      (value "300")
      (footprint "eagle-import:R0805")
      (libsource (lib "eagle-import") (part "R-US_R0805"))
    )
    (comp (ref "R9")
      (value "91")
      (footprint "eagle-import:R0805")
      (libsource (lib "eagle-import") (part "R-US_R0805"))
    )
    (comp (ref "R10")
      (value "5")
      (footprint "eagle-import:R0805")
      (libsource (lib "eagle-import") (part "R-US_R0805"))
    )
    (comp (ref "R11")
      (value "5")
      (footprint "eagle-import:R0805")
      (libsource (lib "eagle-import") (part "R-US_R0805"))
    )
    (comp (ref "SW1")
      (value "450301014042")
      (footprint "eagle-import:SW_450301014042_WRE")
      (fields (field (name "COPYRIGHT") "Copyright (C) 2021 Ultra Librarian. All rights reserved."))
      (libsource (lib "eagle-import") (part "450301014042"))
    )
    (comp (ref "SW2")
      (value "450301014042")
      (footprint "eagle-import:SW_450301014042_WRE")
      (fields (field (name "COPYRIGHT") "Copyright (C) 2021 Ultra Librarian. All rights reserved."))
      (libsource (lib "eagle-import") (part "450301014042"))
    )
    (comp (ref "U3")
      (value "LM62435BPPQRJRRQ1")
      (footprint "eagle-import:VQFN-HR14_RJR_TEX")
      (fields (field (name "COPYRIGHT") "Copyright (C) 2021 Ultra Librarian. All rights reserved."))
      (libsource (lib "eagle-import") (part "LM62435BPPQRJRRQ1"))
    )
    (comp (ref "U5")
      (value "LP2982IM5-3.3/NOPB")
      (footprint "eagle-import:MF05A")
      (fields (field (name "COPYRIGHT") "Copyright (C) 2021 Ultra Librarian. All rights reserved."))
      (libsource (lib "eagle-import") (part "LP2982IM5-3.3/NOPB"))
    )
    (comp (ref "A1")
      (value "MBED_NXP_LPC1768")
      (footprint "eagle-import:MBED_LPC1768")
      (libsource (lib "eagle-import") (part "MBED_NXP_LPC1768"))
    )
    (comp (ref "D5")
      (value "BLUE")
      (footprint "eagle-import:LED0603")
      (libsource (lib "eagle-import") (part "LED-SMD"))
    )
    (comp (ref "D6")
      (value "BLUE")
      (footprint "eagle-import:LED0603")
      (libsource (lib "eagle-import") (part "LED-SMD"))
    )
    (comp (ref "D7")
      (value "LED-SMD")
      (footprint "eagle-import:LED0603")
      (libsource (lib "eagle-import") (part "LED-SMD"))
    )
    (comp (ref "J1")
      (value "2908-05WB-MG")
      (footprint "eagle-import:CONN_3M_2900")
      (fields (field (name "COPYRIGHT") "Copyright (C) 2021 Ultra Librarian. All rights reserved."))
      (libsource (lib "eagle-import") (part "2908-05WB-MG"))
    )
    (comp (ref "JP1")
      (value "PINHD-1X4")
      (footprint "eagle-import:1X04")
      (libsource (lib "eagle-import") (part "PINHD-1X4"))
    )
    (comp (ref "JP2")
      (value "PINHD-1X20")
      (footprint "eagle-import:1X20")
      (libsource (lib "eagle-import") (part "PINHD-1X20"))
    )
    (comp (ref "JP3")
      (value "PINHD-1X20")
      (footprint "eagle-import:1X20")
      (libsource (lib "eagle-import") (part "PINHD-1X20"))
    )
    (comp (ref "JP7")
      (value "PINHD-1X6")
      (footprint "eagle-import:1X06")
      (libsource (lib "eagle-import") (part "PINHD-1X6"))
    )
    (comp (ref "R15")
      (value "1K")
      (footprint "eagle-import:R0805")
      (libsource (lib "eagle-import") (part "R-US_R0805"))
    )
    (comp (ref "R16")
      (value "1k")
      (footprint "eagle-import:R0805")
      (libsource (lib "eagle-import") (part "R-US_R0805"))
    )
    (comp (ref "R17")
      (value "1k")
      (footprint "eagle-import:R0805")
      (libsource (lib "eagle-import") (part "R-US_R0805"))
    )
    (comp (ref "R30")
      (value "10k")
      (footprint "eagle-import:R0805")
      (libsource (lib "eagle-import") (part "R-US_R0805"))
    )
    (comp (ref "R31")
      (value "1k")
      (footprint "eagle-import:R0805")
      (libsource (lib "eagle-import") (part "R-US_R0805"))
    )
    (comp (ref "R32")
      (value "1k")
      (footprint "eagle-import:R0805")
      (libsource (lib "eagle-import") (part "R-US_R0805"))
    )
    (comp (ref "R33")
      (value "10k")
      (footprint "eagle-import:R0805")
      (libsource (lib "eagle-import") (part "R-US_R0805"))
    )
  )
  (nets
    (net (code "1") (name "+3.3-REG") (class "Default")
      (node (ref "R30") (pin "2") (pinfunction "2_2") (pintype "passive"))
      (node (ref "R31") (pin "2") (pinfunction "2_2") (pintype "passive"))
      (node (ref "R32") (pin "2") (pinfunction "2_2") (pintype "passive"))
      (node (ref "R33") (pin "2") (pinfunction "2_2") (pintype "passive"))
    )
    (net (code "2") (name "+3.3V-MBED") (class "Default")
      (node (ref "A1") (pin "VOUT") (pinfunction "VO_VOUT") (pintype "passive"))
      (node (ref "J1") (pin "4") (pinfunction "4_4") (pintype "passive"))
      (node (ref "JP1") (pin "2") (pinfunction "2_2") (pintype "passive"))
      (node (ref "JP2") (pin "20") (pinfunction "20_20") (pintype "passive"))
      (node (ref "R11") (pin "1") (pinfunction "1_1") (pintype "passive"))
    )
    (net (code "3") (name "+3.3V-REG") (class "Default")
      (node (ref "C13") (pin "1") (pinfunction "1_1") (pintype "passive"))
      (node (ref "C14") (pin "1") (pinfunction "1_1") (pintype "passive"))
      (node (ref "C15") (pin "1") (pinfunction "1_1") (pintype "passive"))
      (node (ref "C26") (pin "1") (pinfunction "1_1") (pintype "passive"))
      (node (ref "C27") (pin "1") (pinfunction "1_1") (pintype "passive"))
      (node (ref "R10") (pin "1") (pinfunction "1_1") (pintype "passive"))
      (node (ref "R22") (pin "2") (pinfunction "2_2") (pintype "passive"))
      (node (ref "R23") (pin "2") (pinfunction "2_2") (pintype "passive"))
      (node (ref "U1") (pin "35") (pinfunction "~{PWDN}_35") (pintype "power_in"))
      (node (ref "U1") (pin "48") (pinfunction "DVDD_2_48") (pintype "power_in"))
      (node (ref "U1") (pin "50") (pinfunction "DVDD_50") (pintype "power_in"))
      (node (ref "U2") (pin "35") (pinfunction "~{PWDN}_35") (pintype "power_in"))
      (node (ref "U2") (pin "48") (pinfunction "DVDD_2_48") (pintype "power_in"))
      (node (ref "U2") (pin "50") (pinfunction "DVDD_50") (pintype "power_in"))
      (node (ref "U5") (pin "5") (pinfunction "VOUT_5") (pintype "output"))
    )
    (net (code "4") (name "+5V") (class "Default")
      (node (ref "A1") (pin "VIN") (pinfunction "VIN_VIN") (pintype "passive"))
      (node (ref "C1") (pin "1") (pinfunction "1_1") (pintype "passive"))
      (node (ref "C11") (pin "1") (pinfunction "1_1") (pintype "passive"))
      (node (ref "C16") (pin "1") (pinfunction "1_1") (pintype "passive"))
      (node (ref "C17") (pin "1") (pinfunction "1_1") (pintype "passive"))
      (node (ref "C2") (pin "1") (pinfunction "1_1") (pintype "passive"))
      (node (ref "C28") (pin "1") (pinfunction "1_1") (pintype "passive"))
      (node (ref "C29") (pin "1") (pinfunction "1_1") (pintype "passive"))
      (node (ref "C3") (pin "1") (pinfunction "1_1") (pintype "passive"))
      (node (ref "JP3") (pin "2") (pinfunction "2_2") (pintype "passive"))
      (node (ref "JP7") (pin "2") (pinfunction "2_2") (pintype "passive"))
      (node (ref "L1") (pin "2") (pinfunction "2_2") (pintype "passive"))
      (node (ref "R4") (pin "1") (pinfunction "1_1") (pintype "passive"))
      (node (ref "R5") (pin "1") (pinfunction "1_1") (pintype "passive"))
      (node (ref "R9") (pin "1") (pinfunction "1_1") (pintype "passive"))
      (node (ref "U1") (pin "19") (pinfunction "AVDD_2_19") (pintype "power_in"))
      (node (ref "U1") (pin "21") (pinfunction "AVDD_3_21") (pintype "power_in"))
      (node (ref "U1") (pin "22") (pinfunction "AVDD_4_22") (pintype "power_in"))
      (node (ref "U1") (pin "54") (pinfunction "AVDD1_54") (pintype "power_in"))
      (node (ref "U1") (pin "56") (pinfunction "AVDD_5_56") (pintype "power_in"))
      (node (ref "U1") (pin "59") (pinfunction "AVDD_59") (pintype "power_in"))
      (node (ref "U11") (pin "2") (pinfunction "IO2_2") (pintype "bidirectional"))
      (node (ref "U17") (pin "2") (pinfunction "IO2_2") (pintype "bidirectional"))
      (node (ref "U2") (pin "19") (pinfunction "AVDD_2_19") (pintype "power_in"))
      (node (ref "U2") (pin "21") (pinfunction "AVDD_3_21") (pintype "power_in"))
      (node (ref "U2") (pin "22") (pinfunction "AVDD_4_22") (pintype "power_in"))
      (node (ref "U2") (pin "54") (pinfunction "AVDD1_54") (pintype "power_in"))
      (node (ref "U2") (pin "56") (pinfunction "AVDD_5_56") (pintype "power_in"))
      (node (ref "U2") (pin "59") (pinfunction "AVDD_59") (pintype "power_in"))
      (node (ref "U3") (pin "1") (pinfunction "BIAS_1") (pintype "passive"))
      (node (ref "U5") (pin "1") (pinfunction "VIN_1") (pintype "input"))
      (node (ref "U5") (pin "3") (pinfunction "ON/~{OFF}_3") (pintype "passive"))
    )
    (net (code "5") (name "+9V") (class "Default")
      (node (ref "C4") (pin "1") (pinfunction "1_1") (pintype "passive"))
      (node (ref "C5") (pin "1") (pinfunction "1_1") (pintype "passive"))
      (node (ref "C6") (pin "1") (pinfunction "1_1") (pintype "passive"))
      (node (ref "C7") (pin "1") (pinfunction "1_1") (pintype "passive"))
      (node (ref "R1") (pin "2") (pinfunction "2_2") (pintype "passive"))
      (node (ref "R8") (pin "1") (pinfunction "1_1") (pintype "passive"))
      (node (ref "SW2") (pin "1") (pinfunction "1_1") (pintype "passive"))
      (node (ref "U3") (pin "12") (pinfunction "VIN2_12") (pintype "input"))
      (node (ref "U3") (pin "8") (pinfunction "VIN1_8") (pintype "input"))
    )
    (net (code "6") (name "+9V-CON") (class "Default")
      (node (ref "J4") (pin "PWR") (pinfunction "PWR_PWR") (pintype "bidirectional"))
      (node (ref "SW1") (pin "3") (pinfunction "3_3") (pintype "passive"))
    )
    (net (code "7") (name "1N") (class "Default")
      (node (ref "J12") (pin "GND") (pinfunction "GND_GND") (pintype "bidirectional"))
      (node (ref "J12") (pin "GNDBREAK") (pinfunction "GNDBREAK_GNDBREAK") (pintype "bidirectional"))
      (node (ref "R45") (pin "1") (pinfunction "1_1") (pintype "passive"))
      (node (ref "U9") (pin "4") (pinfunction "IO3_4") (pintype "bidirectional"))
    )
    (net (code "8") (name "1P") (class "Default")
      (node (ref "J12") (pin "PWR") (pinfunction "PWR_PWR") (pintype "bidirectional"))
      (node (ref "R45") (pin "2") (pinfunction "2_2") (pintype "passive"))
      (node (ref "U10") (pin "1") (pinfunction "IO1_1") (pintype "bidirectional"))
    )
    (net (code "9") (name "2N") (class "Default")
      (node (ref "J11") (pin "GND") (pinfunction "GND_GND") (pintype "bidirectional"))
      (node (ref "J11") (pin "GNDBREAK") (pinfunction "GNDBREAK_GNDBREAK") (pintype "bidirectional"))
      (node (ref "RA4") (pin "3") (pinfunction "3_3") (pintype "passive"))
      (node (ref "U9") (pin "2") (pinfunction "IO2_2") (pintype "bidirectional"))
    )
    (net (code "10") (name "2P") (class "Default")
      (node (ref "J11") (pin "PWR") (pinfunction "PWR_PWR") (pintype "bidirectional"))
      (node (ref "RA4") (pin "4") (pinfunction "4_4") (pintype "passive"))
      (node (ref "U9") (pin "5") (pinfunction "IO4_5") (pintype "bidirectional"))
    )
    (net (code "11") (name "3N") (class "Default")
      (node (ref "J10") (pin "GND") (pinfunction "GND_GND") (pintype "bidirectional"))
      (node (ref "J10") (pin "GNDBREAK") (pinfunction "GNDBREAK_GNDBREAK") (pintype "bidirectional"))
      (node (ref "RA4") (pin "1") (pinfunction "1_1") (pintype "passive"))
      (node (ref "U8") (pin "4") (pinfunction "IO3_4") (pintype "bidirectional"))
    )
    (net (code "12") (name "3P") (class "Default")
      (node (ref "J10") (pin "PWR") (pinfunction "PWR_PWR") (pintype "bidirectional"))
      (node (ref "RA4") (pin "2") (pinfunction "2_2") (pintype "passive"))
      (node (ref "U9") (pin "1") (pinfunction "IO1_1") (pintype "bidirectional"))
    )
    (net (code "13") (name "4N") (class "Default")
      (node (ref "J9") (pin "GND") (pinfunction "GND_GND") (pintype "bidirectional"))
      (node (ref "J9") (pin "GNDBREAK") (pinfunction "GNDBREAK_GNDBREAK") (pintype "bidirectional"))
      (node (ref "RA3") (pin "3") (pinfunction "3_3") (pintype "passive"))
      (node (ref "U8") (pin "2") (pinfunction "IO2_2") (pintype "bidirectional"))
    )
    (net (code "14") (name "4P") (class "Default")
      (node (ref "J9") (pin "PWR") (pinfunction "PWR_PWR") (pintype "bidirectional"))
      (node (ref "RA3") (pin "4") (pinfunction "4_4") (pintype "passive"))
      (node (ref "U8") (pin "5") (pinfunction "IO4_5") (pintype "bidirectional"))
    )
    (net (code "15") (name "5N") (class "Default")
      (node (ref "J8") (pin "GND") (pinfunction "GND_GND") (pintype "bidirectional"))
      (node (ref "J8") (pin "GNDBREAK") (pinfunction "GNDBREAK_GNDBREAK") (pintype "bidirectional"))
      (node (ref "RA3") (pin "1") (pinfunction "1_1") (pintype "passive"))
      (node (ref "U7") (pin "4") (pinfunction "IO3_4") (pintype "bidirectional"))
    )
    (net (code "16") (name "5P") (class "Default")
      (node (ref "J8") (pin "PWR") (pinfunction "PWR_PWR") (pintype "bidirectional"))
      (node (ref "RA3") (pin "2") (pinfunction "2_2") (pintype "passive"))
      (node (ref "U8") (pin "1") (pinfunction "IO1_1") (pintype "bidirectional"))
    )
    (net (code "17") (name "6N") (class "Default")
      (node (ref "J7") (pin "GND") (pinfunction "GND_GND") (pintype "bidirectional"))
      (node (ref "J7") (pin "GNDBREAK") (pinfunction "GNDBREAK_GNDBREAK") (pintype "bidirectional"))
      (node (ref "RA2") (pin "3") (pinfunction "3_3") (pintype "passive"))
      (node (ref "U7") (pin "2") (pinfunction "IO2_2") (pintype "bidirectional"))
    )
    (net (code "18") (name "6P") (class "Default")
      (node (ref "J7") (pin "PWR") (pinfunction "PWR_PWR") (pintype "bidirectional"))
      (node (ref "RA2") (pin "4") (pinfunction "4_4") (pintype "passive"))
      (node (ref "U7") (pin "5") (pinfunction "IO4_5") (pintype "bidirectional"))
    )
    (net (code "19") (name "7N") (class "Default")
      (node (ref "J6") (pin "GND") (pinfunction "GND_GND") (pintype "bidirectional"))
      (node (ref "J6") (pin "GNDBREAK") (pinfunction "GNDBREAK_GNDBREAK") (pintype "bidirectional"))
      (node (ref "RA2") (pin "1") (pinfunction "1_1") (pintype "passive"))
      (node (ref "U6") (pin "4") (pinfunction "IO3_4") (pintype "bidirectional"))
    )
    (net (code "20") (name "7P") (class "Default")
      (node (ref "J6") (pin "PWR") (pinfunction "PWR_PWR") (pintype "bidirectional"))
      (node (ref "RA2") (pin "2") (pinfunction "2_2") (pintype "passive"))
      (node (ref "U7") (pin "1") (pinfunction "IO1_1") (pintype "bidirectional"))
    )
    (net (code "21") (name "8N") (class "Default")
      (node (ref "J5") (pin "GND") (pinfunction "GND_GND") (pintype "bidirectional"))
      (node (ref "J5") (pin "GNDBREAK") (pinfunction "GNDBREAK_GNDBREAK") (pintype "bidirectional"))
      (node (ref "RA1") (pin "3") (pinfunction "3_3") (pintype "passive"))
      (node (ref "U6") (pin "2") (pinfunction "IO2_2") (pintype "bidirectional"))
    )
    (net (code "22") (name "8P") (class "Default")
      (node (ref "J5") (pin "PWR") (pinfunction "PWR_PWR") (pintype "bidirectional"))
      (node (ref "RA1") (pin "4") (pinfunction "4_4") (pintype "passive"))
      (node (ref "U6") (pin "5") (pinfunction "IO4_5") (pintype "bidirectional"))
    )
    (net (code "23") (name "9N") (class "Default")
      (node (ref "J20") (pin "GND") (pinfunction "GND_GND") (pintype "bidirectional"))
      (node (ref "J20") (pin "GNDBREAK") (pinfunction "GNDBREAK_GNDBREAK") (pintype "bidirectional"))
      (node (ref "R14") (pin "1") (pinfunction "1_1") (pintype "passive"))
      (node (ref "U15") (pin "4") (pinfunction "IO3_4") (pintype "bidirectional"))
    )
    (net (code "24") (name "9P") (class "Default")
      (node (ref "J20") (pin "PWR") (pinfunction "PWR_PWR") (pintype "bidirectional"))
      (node (ref "R14") (pin "2") (pinfunction "2_2") (pintype "passive"))
      (node (ref "U16") (pin "1") (pinfunction "IO1_1") (pintype "bidirectional"))
    )
    (net (code "25") (name "10N") (class "Default")
      (node (ref "J19") (pin "GND") (pinfunction "GND_GND") (pintype "bidirectional"))
      (node (ref "J19") (pin "GNDBREAK") (pinfunction "GNDBREAK_GNDBREAK") (pintype "bidirectional"))
      (node (ref "RA8") (pin "3") (pinfunction "3_3") (pintype "passive"))
      (node (ref "U15") (pin "2") (pinfunction "IO2_2") (pintype "bidirectional"))
    )
    (net (code "26") (name "10P") (class "Default")
      (node (ref "J19") (pin "PWR") (pinfunction "PWR_PWR") (pintype "bidirectional"))
      (node (ref "RA8") (pin "4") (pinfunction "4_4") (pintype "passive"))
      (node (ref "U15") (pin "5") (pinfunction "IO4_5") (pintype "bidirectional"))
    )
    (net (code "27") (name "11N") (class "Default")
      (node (ref "J18") (pin "GND") (pinfunction "GND_GND") (pintype "bidirectional"))
      (node (ref "J18") (pin "GNDBREAK") (pinfunction "GNDBREAK_GNDBREAK") (pintype "bidirectional"))
      (node (ref "RA8") (pin "1") (pinfunction "1_1") (pintype "passive"))
      (node (ref "U14") (pin "4") (pinfunction "IO3_4") (pintype "bidirectional"))
    )
    (net (code "28") (name "11P") (class "Default")
      (node (ref "J18") (pin "PWR") (pinfunction "PWR_PWR") (pintype "bidirectional"))
      (node (ref "RA8") (pin "2") (pinfunction "2_2") (pintype "passive"))
      (node (ref "U15") (pin "1") (pinfunction "IO1_1") (pintype "bidirectional"))
    )
    (net (code "29") (name "12N") (class "Default")
      (node (ref "J17") (pin "GND") (pinfunction "GND_GND") (pintype "bidirectional"))
      (node (ref "J17") (pin "GNDBREAK") (pinfunction "GNDBREAK_GNDBREAK") (pintype "bidirectional"))
      (node (ref "RA7") (pin "3") (pinfunction "3_3") (pintype "passive"))
      (node (ref "U14") (pin "2") (pinfunction "IO2_2") (pintype "bidirectional"))
    )
    (net (code "30") (name "12P") (class "Default")
      (node (ref "J17") (pin "PWR") (pinfunction "PWR_PWR") (pintype "bidirectional"))
      (node (ref "RA7") (pin "4") (pinfunction "4_4") (pintype "passive"))
      (node (ref "U14") (pin "5") (pinfunction "IO4_5") (pintype "bidirectional"))
    )
    (net (code "31") (name "13N") (class "Default")
      (node (ref "J16") (pin "GND") (pinfunction "GND_GND") (pintype "bidirectional"))
      (node (ref "J16") (pin "GNDBREAK") (pinfunction "GNDBREAK_GNDBREAK") (pintype "bidirectional"))
      (node (ref "RA7") (pin "1") (pinfunction "1_1") (pintype "passive"))
      (node (ref "U13") (pin "4") (pinfunction "IO3_4") (pintype "bidirectional"))
    )
    (net (code "32") (name "13P") (class "Default")
      (node (ref "J16") (pin "PWR") (pinfunction "PWR_PWR") (pintype "bidirectional"))
      (node (ref "RA7") (pin "2") (pinfunction "2_2") (pintype "passive"))
      (node (ref "U14") (pin "1") (pinfunction "IO1_1") (pintype "bidirectional"))
    )
    (net (code "33") (name "14N") (class "Default")
      (node (ref "J15") (pin "GND") (pinfunction "GND_GND") (pintype "bidirectional"))
      (node (ref "J15") (pin "GNDBREAK") (pinfunction "GNDBREAK_GNDBREAK") (pintype "bidirectional"))
      (node (ref "RA6") (pin "3") (pinfunction "3_3") (pintype "passive"))
      (node (ref "U13") (pin "2") (pinfunction "IO2_2") (pintype "bidirectional"))
    )
    (net (code "34") (name "14P") (class "Default")
      (node (ref "J15") (pin "PWR") (pinfunction "PWR_PWR") (pintype "bidirectional"))
      (node (ref "RA6") (pin "4") (pinfunction "4_4") (pintype "passive"))
      (node (ref "U13") (pin "5") (pinfunction "IO4_5") (pintype "bidirectional"))
    )
    (net (code "35") (name "15N") (class "Default")
      (node (ref "J14") (pin "GND") (pinfunction "GND_GND") (pintype "bidirectional"))
      (node (ref "J14") (pin "GNDBREAK") (pinfunction "GNDBREAK_GNDBREAK") (pintype "bidirectional"))
      (node (ref "RA6") (pin "1") (pinfunction "1_1") (pintype "passive"))
      (node (ref "U12") (pin "4") (pinfunction "IO3_4") (pintype "bidirectional"))
    )
    (net (code "36") (name "15P") (class "Default")
      (node (ref "J14") (pin "PWR") (pinfunction "PWR_PWR") (pintype "bidirectional"))
      (node (ref "RA6") (pin "2") (pinfunction "2_2") (pintype "passive"))
      (node (ref "U13") (pin "1") (pinfunction "IO1_1") (pintype "bidirectional"))
    )
    (net (code "37") (name "16N") (class "Default")
      (node (ref "J13") (pin "GND") (pinfunction "GND_GND") (pintype "bidirectional"))
      (node (ref "J13") (pin "GNDBREAK") (pinfunction "GNDBREAK_GNDBREAK") (pintype "bidirectional"))
      (node (ref "RA5") (pin "3") (pinfunction "3_3") (pintype "passive"))
      (node (ref "U12") (pin "2") (pinfunction "IO2_2") (pintype "bidirectional"))
    )
    (net (code "38") (name "16P") (class "Default")
      (node (ref "J13") (pin "PWR") (pinfunction "PWR_PWR") (pintype "bidirectional"))
      (node (ref "RA5") (pin "4") (pinfunction "4_4") (pintype "passive"))
      (node (ref "U12") (pin "5") (pinfunction "IO4_5") (pintype "bidirectional"))
    )
    (net (code "39") (name "AIN1N") (class "Default")
      (node (ref "CA5") (pin "8") (pinfunction "8_8") (pintype "passive"))
      (node (ref "R45") (pin "8") (pinfunction "8_8") (pintype "passive"))
      (node (ref "U1") (pin "15") (pinfunction "IN1N_15") (pintype "input"))
    )
    (net (code "40") (name "AIN1P") (class "Default")
      (node (ref "CA5") (pin "7") (pinfunction "7_7") (pintype "passive"))
      (node (ref "R45") (pin "7") (pinfunction "7_7") (pintype "passive"))
      (node (ref "U1") (pin "16") (pinfunction "IN1P_16") (pintype "input"))
    )
    (net (code "41") (name "AIN2N") (class "Default")
      (node (ref "CA4") (pin "6") (pinfunction "6_6") (pintype "passive"))
      (node (ref "RA4") (pin "6") (pinfunction "6_6") (pintype "passive"))
      (node (ref "U1") (pin "13") (pinfunction "IN2N_13") (pintype "input"))
    )
    (net (code "42") (name "AIN2P") (class "Default")
      (node (ref "CA4") (pin "5") (pinfunction "5_5") (pintype "passive"))
      (node (ref "RA4") (pin "5") (pinfunction "5_5") (pintype "passive"))
      (node (ref "U1") (pin "14") (pinfunction "IN2P_14") (pintype "input"))
    )
    (net (code "43") (name "AIN3N") (class "Default")
      (node (ref "CA4") (pin "8") (pinfunction "8_8") (pintype "passive"))
      (node (ref "RA4") (pin "8") (pinfunction "8_8") (pintype "passive"))
      (node (ref "U1") (pin "11") (pinfunction "IN3N_11") (pintype "input"))
    )
    (net (code "44") (name "AIN3P") (class "Default")
      (node (ref "CA4") (pin "7") (pinfunction "7_7") (pintype "passive"))
      (node (ref "RA4") (pin "7") (pinfunction "7_7") (pintype "passive"))
      (node (ref "U1") (pin "12") (pinfunction "IN3P_12") (pintype "input"))
    )
    (net (code "45") (name "AIN4N") (class "Default")
      (node (ref "CA3") (pin "6") (pinfunction "6_6") (pintype "passive"))
      (node (ref "RA3") (pin "6") (pinfunction "6_6") (pintype "passive"))
      (node (ref "U1") (pin "9") (pinfunction "IN4N_9") (pintype "input"))
    )
    (net (code "46") (name "AIN4P") (class "Default")
      (node (ref "CA3") (pin "5") (pinfunction "5_5") (pintype "passive"))
      (node (ref "RA3") (pin "5") (pinfunction "5_5") (pintype "passive"))
      (node (ref "U1") (pin "10") (pinfunction "IN4P_10") (pintype "input"))
    )
    (net (code "47") (name "AIN5N") (class "Default")
      (node (ref "CA3") (pin "8") (pinfunction "8_8") (pintype "passive"))
      (node (ref "RA3") (pin "8") (pinfunction "8_8") (pintype "passive"))
      (node (ref "U1") (pin "7") (pinfunction "IN5N_7") (pintype "input"))
    )
    (net (code "48") (name "AIN5P") (class "Default")
      (node (ref "CA3") (pin "7") (pinfunction "7_7") (pintype "passive"))
      (node (ref "RA3") (pin "7") (pinfunction "7_7") (pintype "passive"))
      (node (ref "U1") (pin "8") (pinfunction "IN5P_8") (pintype "input"))
    )
    (net (code "49") (name "AIN6N") (class "Default")
      (node (ref "CA2") (pin "6") (pinfunction "6_6") (pintype "passive"))
      (node (ref "RA2") (pin "6") (pinfunction "6_6") (pintype "passive"))
      (node (ref "U1") (pin "5") (pinfunction "IN6N_5") (pintype "input"))
    )
    (net (code "50") (name "AIN6P") (class "Default")
      (node (ref "CA2") (pin "5") (pinfunction "5_5") (pintype "passive"))
      (node (ref "RA2") (pin "5") (pinfunction "5_5") (pintype "passive"))
      (node (ref "U1") (pin "6") (pinfunction "IN6P_6") (pintype "input"))
    )
    (net (code "51") (name "AIN7N") (class "Default")
      (node (ref "CA2") (pin "8") (pinfunction "8_8") (pintype "passive"))
      (node (ref "RA2") (pin "8") (pinfunction "8_8") (pintype "passive"))
      (node (ref "U1") (pin "3") (pinfunction "IN7N_3") (pintype "input"))
    )
    (net (code "52") (name "AIN7P") (class "Default")
      (node (ref "CA2") (pin "7") (pinfunction "7_7") (pintype "passive"))
      (node (ref "RA2") (pin "7") (pinfunction "7_7") (pintype "passive"))
      (node (ref "U1") (pin "4") (pinfunction "IN7P_4") (pintype "input"))
    )
    (net (code "53") (name "AIN8N") (class "Default")
      (node (ref "CA1") (pin "6") (pinfunction "6_6") (pintype "passive"))
      (node (ref "RA1") (pin "6") (pinfunction "6_6") (pintype "passive"))
      (node (ref "U1") (pin "1") (pinfunction "IN8N_1") (pintype "input"))
    )
    (net (code "54") (name "AIN8P") (class "Default")
      (node (ref "CA1") (pin "5") (pinfunction "5_5") (pintype "passive"))
      (node (ref "RA1") (pin "5") (pinfunction "5_5") (pintype "passive"))
      (node (ref "U1") (pin "2") (pinfunction "IN8P_2") (pintype "input"))
    )
    (net (code "55") (name "AIN9N") (class "Default")
      (node (ref "CA10") (pin "8") (pinfunction "8_8") (pintype "passive"))
      (node (ref "R14") (pin "8") (pinfunction "8_8") (pintype "passive"))
      (node (ref "U2") (pin "15") (pinfunction "IN1N_15") (pintype "input"))
    )
    (net (code "56") (name "AIN9P") (class "Default")
      (node (ref "CA10") (pin "7") (pinfunction "7_7") (pintype "passive"))
      (node (ref "R14") (pin "7") (pinfunction "7_7") (pintype "passive"))
      (node (ref "U2") (pin "16") (pinfunction "IN1P_16") (pintype "input"))
    )
    (net (code "57") (name "AIN10N") (class "Default")
      (node (ref "CA9") (pin "6") (pinfunction "6_6") (pintype "passive"))
      (node (ref "RA8") (pin "6") (pinfunction "6_6") (pintype "passive"))
      (node (ref "U2") (pin "13") (pinfunction "IN2N_13") (pintype "input"))
    )
    (net (code "58") (name "AIN10P") (class "Default")
      (node (ref "CA9") (pin "5") (pinfunction "5_5") (pintype "passive"))
      (node (ref "RA8") (pin "5") (pinfunction "5_5") (pintype "passive"))
      (node (ref "U2") (pin "14") (pinfunction "IN2P_14") (pintype "input"))
    )
    (net (code "59") (name "AIN11N") (class "Default")
      (node (ref "CA9") (pin "8") (pinfunction "8_8") (pintype "passive"))
      (node (ref "RA8") (pin "8") (pinfunction "8_8") (pintype "passive"))
      (node (ref "U2") (pin "11") (pinfunction "IN3N_11") (pintype "input"))
    )
    (net (code "60") (name "AIN11P") (class "Default")
      (node (ref "CA9") (pin "7") (pinfunction "7_7") (pintype "passive"))
      (node (ref "RA8") (pin "7") (pinfunction "7_7") (pintype "passive"))
      (node (ref "U2") (pin "12") (pinfunction "IN3P_12") (pintype "input"))
    )
    (net (code "61") (name "AIN12N") (class "Default")
      (node (ref "CA8") (pin "6") (pinfunction "6_6") (pintype "passive"))
      (node (ref "RA7") (pin "6") (pinfunction "6_6") (pintype "passive"))
      (node (ref "U2") (pin "9") (pinfunction "IN4N_9") (pintype "input"))
    )
    (net (code "62") (name "AIN12P") (class "Default")
      (node (ref "CA8") (pin "5") (pinfunction "5_5") (pintype "passive"))
      (node (ref "RA7") (pin "5") (pinfunction "5_5") (pintype "passive"))
      (node (ref "U2") (pin "10") (pinfunction "IN4P_10") (pintype "input"))
    )
    (net (code "63") (name "AIN13N") (class "Default")
      (node (ref "CA8") (pin "8") (pinfunction "8_8") (pintype "passive"))
      (node (ref "RA7") (pin "8") (pinfunction "8_8") (pintype "passive"))
      (node (ref "U2") (pin "7") (pinfunction "IN5N_7") (pintype "input"))
    )
    (net (code "64") (name "AIN13P") (class "Default")
      (node (ref "CA8") (pin "7") (pinfunction "7_7") (pintype "passive"))
      (node (ref "RA7") (pin "7") (pinfunction "7_7") (pintype "passive"))
      (node (ref "U2") (pin "8") (pinfunction "IN5P_8") (pintype "input"))
    )
    (net (code "65") (name "AIN14N") (class "Default")
      (node (ref "CA7") (pin "6") (pinfunction "6_6") (pintype "passive"))
      (node (ref "RA6") (pin "6") (pinfunction "6_6") (pintype "passive"))
      (node (ref "U2") (pin "5") (pinfunction "IN6N_5") (pintype "input"))
    )
    (net (code "66") (name "AIN14P") (class "Default")
      (node (ref "CA7") (pin "5") (pinfunction "5_5") (pintype "passive"))
      (node (ref "RA6") (pin "5") (pinfunction "5_5") (pintype "passive"))
      (node (ref "U2") (pin "6") (pinfunction "IN6P_6") (pintype "input"))
    )
    (net (code "67") (name "AIN15N") (class "Default")
      (node (ref "CA7") (pin "8") (pinfunction "8_8") (pintype "passive"))
      (node (ref "RA6") (pin "8") (pinfunction "8_8") (pintype "passive"))
      (node (ref "U2") (pin "3") (pinfunction "IN7N_3") (pintype "input"))
    )
    (net (code "68") (name "AIN15P") (class "Default")
      (node (ref "CA7") (pin "7") (pinfunction "7_7") (pintype "passive"))
      (node (ref "RA6") (pin "7") (pinfunction "7_7") (pintype "passive"))
      (node (ref "U2") (pin "4") (pinfunction "IN7P_4") (pintype "input"))
    )
    (net (code "69") (name "AIN16N") (class "Default")
      (node (ref "CA6") (pin "6") (pinfunction "6_6") (pintype "passive"))
      (node (ref "RA5") (pin "6") (pinfunction "6_6") (pintype "passive"))
      (node (ref "U2") (pin "1") (pinfunction "IN8N_1") (pintype "input"))
    )
    (net (code "70") (name "AIN16P") (class "Default")
      (node (ref "CA6") (pin "5") (pinfunction "5_5") (pintype "passive"))
      (node (ref "RA5") (pin "5") (pinfunction "5_5") (pintype "passive"))
      (node (ref "U2") (pin "2") (pinfunction "IN8P_2") (pintype "input"))
    )
    (net (code "71") (name "B1") (class "Default")
      (node (ref "A1") (pin "VB") (pinfunction "VB_VB") (pintype "passive"))
      (node (ref "JP3") (pin "3") (pinfunction "3_3") (pintype "passive"))
    )
    (net (code "72") (name "B2") (class "Default")
      (node (ref "A1") (pin "NR") (pinfunction "NR_NR") (pintype "passive"))
      (node (ref "JP3") (pin "4") (pinfunction "4_4") (pintype "passive"))
    )
    (net (code "73") (name "B5") (class "Default")
      (node (ref "A1") (pin "P$21") (pinfunction "P21_P$21") (pintype "passive"))
      (node (ref "JP2") (pin "1") (pinfunction "1_1") (pintype "passive"))
    )
    (net (code "74") (name "B6") (class "Default")
      (node (ref "A1") (pin "P$23") (pinfunction "P23_P$23") (pintype "passive"))
      (node (ref "JP2") (pin "3") (pinfunction "3_3") (pintype "passive"))
    )
    (net (code "75") (name "B7") (class "Default")
      (node (ref "A1") (pin "P$24") (pinfunction "P24_P$24") (pintype "passive"))
      (node (ref "JP2") (pin "4") (pinfunction "4_4") (pintype "passive"))
    )
    (net (code "76") (name "B8") (class "Default")
      (node (ref "A1") (pin "P$26") (pinfunction "P26_P$26") (pintype "passive"))
      (node (ref "JP2") (pin "6") (pinfunction "6_6") (pintype "passive"))
    )
    (net (code "77") (name "B9") (class "Default")
      (node (ref "A1") (pin "P$30") (pinfunction "P30_P$30") (pintype "passive"))
      (node (ref "JP2") (pin "10") (pinfunction "10_10") (pintype "passive"))
    )
    (net (code "78") (name "B10") (class "Default")
      (node (ref "A1") (pin "D+") (pinfunction "D+_D+") (pintype "passive"))
      (node (ref "JP2") (pin "11") (pinfunction "11_11") (pintype "passive"))
    )
    (net (code "79") (name "B11") (class "Default")
      (node (ref "A1") (pin "D-") (pinfunction "D-_D-") (pintype "passive"))
      (node (ref "JP2") (pin "12") (pinfunction "12_12") (pintype "passive"))
    )
    (net (code "80") (name "B12") (class "Default")
      (node (ref "A1") (pin "TD+") (pinfunction "TD+_TD+") (pintype "passive"))
      (node (ref "JP2") (pin "13") (pinfunction "13_13") (pintype "passive"))
    )
    (net (code "81") (name "B13") (class "Default")
      (node (ref "A1") (pin "TD-") (pinfunction "TD-_TD-") (pintype "passive"))
      (node (ref "JP2") (pin "14") (pinfunction "14_14") (pintype "passive"))
    )
    (net (code "82") (name "B14") (class "Default")
      (node (ref "A1") (pin "RD+") (pinfunction "RD+_RD+") (pintype "passive"))
      (node (ref "JP2") (pin "15") (pinfunction "15_15") (pintype "passive"))
    )
    (net (code "83") (name "B15") (class "Default")
      (node (ref "A1") (pin "RD-") (pinfunction "RD-_RD-") (pintype "passive"))
      (node (ref "JP2") (pin "16") (pinfunction "16_16") (pintype "passive"))
    )
    (net (code "84") (name "B16") (class "Default")
      (node (ref "A1") (pin "IF+") (pinfunction "IF+_IF+") (pintype "passive"))
      (node (ref "JP2") (pin "17") (pinfunction "17_17") (pintype "passive"))
    )
    (net (code "85") (name "B17") (class "Default")
      (node (ref "A1") (pin "IF-") (pinfunction "IF-_IF-") (pintype "passive"))
      (node (ref "JP2") (pin "18") (pinfunction "18_18") (pintype "passive"))
    )
    (net (code "86") (name "B18") (class "Default")
      (node (ref "A1") (pin "VU") (pinfunction "VU_VU") (pintype "passive"))
      (node (ref "JP2") (pin "19") (pinfunction "19_19") (pintype "passive"))
    )
    (net (code "87") (name "BATT_SWITCH") (class "Default")
      (node (ref "SW1") (pin "1") (pinfunction "1_1") (pintype "passive"))
      (node (ref "SW2") (pin "3") (pinfunction "3_3") (pintype "passive"))
    )
    (net (code "88") (name "BIAS") (class "Default")
      (node (ref "J21") (pin "GND") (pinfunction "GND_GND") (pintype "bidirectional"))
      (node (ref "J21") (pin "GNDBREAK") (pinfunction "GNDBREAK_GNDBREAK") (pintype "bidirectional"))
      (node (ref "J21") (pin "PWR") (pinfunction "PWR_PWR") (pintype "bidirectional"))
      (node (ref "RA1") (pin "1") (pinfunction "1_1") (pintype "passive"))
      (node (ref "U11") (pin "4") (pinfunction "IO3_4") (pintype "bidirectional"))
    )
    (net (code "89") (name "BIAS_1") (class "Default")
      (node (ref "J23") (pin "GND") (pinfunction "GND_GND") (pintype "bidirectional"))
      (node (ref "J23") (pin "GNDBREAK") (pinfunction "GNDBREAK_GNDBREAK") (pintype "bidirectional"))
      (node (ref "J23") (pin "PWR") (pinfunction "PWR_PWR") (pintype "bidirectional"))
      (node (ref "RA5") (pin "1") (pinfunction "1_1") (pintype "passive"))
      (node (ref "U17") (pin "4") (pinfunction "IO3_4") (pintype "bidirectional"))
    )
    (net (code "90") (name "BIAS_DRV") (class "Default")
      (node (ref "C25") (pin "1") (pinfunction "1_1") (pintype "passive"))
      (node (ref "CA1") (pin "8") (pinfunction "8_8") (pintype "passive"))
      (node (ref "R12") (pin "1") (pinfunction "1_1") (pintype "passive"))
      (node (ref "RA1") (pin "8") (pinfunction "8_8") (pintype "passive"))
    )
    (net (code "91") (name "BIAS_DRV_1") (class "Default")
      (node (ref "C37") (pin "1") (pinfunction "1_1") (pintype "passive"))
      (node (ref "CA6") (pin "8") (pinfunction "8_8") (pintype "passive"))
      (node (ref "R13") (pin "1") (pinfunction "1_1") (pintype "passive"))
      (node (ref "RA5") (pin "8") (pinfunction "8_8") (pintype "passive"))
    )
    (net (code "92") (name "BIAS_INV") (class "Default")
      (node (ref "JP4") (pin "2") (pinfunction "2_2") (pintype "passive"))
      (node (ref "U1") (pin "61") (pinfunction "BIASINV_61") (pintype "bidirectional"))
    )
    (net (code "93") (name "BIAS_INV_1") (class "Default")
      (node (ref "JP5") (pin "2") (pinfunction "2_2") (pintype "passive"))
      (node (ref "U2") (pin "61") (pinfunction "BIASINV_61") (pintype "bidirectional"))
    )
    (net (code "94") (name "BLE_EN") (class "Default")
      (node (ref "A1") (pin "P$17") (pinfunction "P17_P$17") (pintype "passive"))
      (node (ref "JP3") (pin "17") (pinfunction "17_17") (pintype "passive"))
      (node (ref "JP7") (pin "1") (pinfunction "1_1") (pintype "passive"))
    )
    (net (code "95") (name "BLE_RX") (class "Default")
      (node (ref "A1") (pin "P$9") (pinfunction "P9_P$9") (pintype "passive"))
      (node (ref "JP3") (pin "9") (pinfunction "9_9") (pintype "passive"))
      (node (ref "JP7") (pin "5") (pinfunction "5_5") (pintype "passive"))
    )
    (net (code "96") (name "BLE_STATE") (class "Default")
      (node (ref "A1") (pin "P$18") (pinfunction "P18_P$18") (pintype "passive"))
      (node (ref "JP3") (pin "18") (pinfunction "18_18") (pintype "passive"))
      (node (ref "JP7") (pin "6") (pinfunction "6_6") (pintype "passive"))
    )
    (net (code "97") (name "BLE_TX") (class "Default")
      (node (ref "A1") (pin "P$10") (pinfunction "P10_P$10") (pintype "passive"))
      (node (ref "JP3") (pin "10") (pinfunction "10_10") (pintype "passive"))
      (node (ref "JP7") (pin "4") (pinfunction "4_4") (pintype "passive"))
    )
    (net (code "98") (name "CLK_ADS") (class "Default")
      (node (ref "R18") (pin "2") (pinfunction "2_2") (pintype "passive"))
      (node (ref "R19") (pin "2") (pinfunction "2_2") (pintype "passive"))
      (node (ref "U1") (pin "37") (pinfunction "CLK_37") (pintype "input"))
    )
    (net (code "99") (name "DEBUG_1") (class "Default")
      (node (ref "A1") (pin "P$29") (pinfunction "P29_P$29") (pintype "passive"))
      (node (ref "JP2") (pin "9") (pinfunction "9_9") (pintype "passive"))
      (node (ref "R15") (pin "1") (pinfunction "1_1") (pintype "passive"))
    )
    (net (code "100") (name "DEBUG_2") (class "Default")
      (node (ref "A1") (pin "P$25") (pinfunction "P25_P$25") (pintype "passive"))
      (node (ref "JP2") (pin "5") (pinfunction "5_5") (pintype "passive"))
      (node (ref "R16") (pin "1") (pinfunction "1_1") (pintype "passive"))
    )
    (net (code "101") (name "DEBUG_3") (class "Default")
      (node (ref "A1") (pin "P$22") (pinfunction "P22_P$22") (pintype "passive"))
      (node (ref "JP2") (pin "2") (pinfunction "2_2") (pintype "passive"))
      (node (ref "R17") (pin "1") (pinfunction "1_1") (pintype "passive"))
    )
    (net (code "102") (name "GND") (class "Default")
      (node (ref "A1") (pin "GND") (pinfunction "GND_GND") (pintype "passive"))
      (node (ref "C1") (pin "2") (pinfunction "2_2") (pintype "passive"))
      (node (ref "C11") (pin "2") (pinfunction "2_2") (pintype "passive"))
      (node (ref "C12") (pin "2") (pinfunction "2_2") (pintype "passive"))
      (node (ref "C13") (pin "2") (pinfunction "2_2") (pintype "passive"))
      (node (ref "C14") (pin "2") (pinfunction "2_2") (pintype "passive"))
      (node (ref "C15") (pin "2") (pinfunction "2_2") (pintype "passive"))
      (node (ref "C16") (pin "2") (pinfunction "2_2") (pintype "passive"))
      (node (ref "C17") (pin "2") (pinfunction "2_2") (pintype "passive"))
      (node (ref "C18") (pin "2") (pinfunction "2_2") (pintype "passive"))
      (node (ref "C19") (pin "2") (pinfunction "2_2") (pintype "passive"))
      (node (ref "C2") (pin "2") (pinfunction "2_2") (pintype "passive"))
      (node (ref "C20") (pin "2") (pinfunction "2_2") (pintype "passive"))
      (node (ref "C21") (pin "2") (pinfunction "2_2") (pintype "passive"))
      (node (ref "C22") (pin "2") (pinfunction "2_2") (pintype "passive"))
      (node (ref "C23") (pin "2") (pinfunction "2_2") (pintype "passive"))
      (node (ref "C24") (pin "2") (pinfunction "2_2") (pintype "passive"))
      (node (ref "C26") (pin "2") (pinfunction "2_2") (pintype "passive"))
      (node (ref "C27") (pin "2") (pinfunction "2_2") (pintype "passive"))
      (node (ref "C28") (pin "2") (pinfunction "2_2") (pintype "passive"))
      (node (ref "C29") (pin "2") (pinfunction "2_2") (pintype "passive"))
      (node (ref "C3") (pin "2") (pinfunction "2_2") (pintype "passive"))
      (node (ref "C30") (pin "2") (pinfunction "2_2") (pintype "passive"))
      (node (ref "C31") (pin "2") (pinfunction "2_2") (pintype "passive"))
      (node (ref "C32") (pin "2") (pinfunction "2_2") (pintype "passive"))
      (node (ref "C33") (pin "2") (pinfunction "2_2") (pintype "passive"))
      (node (ref "C34") (pin "2") (pinfunction "2_2") (pintype "passive"))
      (node (ref "C35") (pin "2") (pinfunction "2_2") (pintype "passive"))
      (node (ref "C36") (pin "2") (pinfunction "2_2") (pintype "passive"))
      (node (ref "C4") (pin "2") (pinfunction "2_2") (pintype "passive"))
      (node (ref "C5") (pin "2") (pinfunction "2_2") (pintype "passive"))
      (node (ref "C6") (pin "2") (pinfunction "2_2") (pintype "passive"))
      (node (ref "C7") (pin "2") (pinfunction "2_2") (pintype "passive"))
      (node (ref "C9") (pin "2") (pinfunction "2_2") (pintype "passive"))
      (node (ref "CA1") (pin "1") (pinfunction "1_1") (pintype "passive"))
      (node (ref "CA1") (pin "2") (pinfunction "2_2") (pintype "passive"))
      (node (ref "CA1") (pin "3") (pinfunction "3_3") (pintype "passive"))
      (node (ref "CA1") (pin "4") (pinfunction "4_4") (pintype "passive"))
      (node (ref "CA1") (pin "7") (pinfunction "7_7") (pintype "passive"))
      (node (ref "CA10") (pin "1") (pinfunction "1_1") (pintype "passive"))
      (node (ref "CA10") (pin "2") (pinfunction "2_2") (pintype "passive"))
      (node (ref "CA10") (pin "3") (pinfunction "3_3") (pintype "passive"))
      (node (ref "CA10") (pin "4") (pinfunction "4_4") (pintype "passive"))
      (node (ref "CA2") (pin "1") (pinfunction "1_1") (pintype "passive"))
      (node (ref "CA2") (pin "2") (pinfunction "2_2") (pintype "passive"))
      (node (ref "CA2") (pin "3") (pinfunction "3_3") (pintype "passive"))
      (node (ref "CA2") (pin "4") (pinfunction "4_4") (pintype "passive"))
      (node (ref "CA3") (pin "1") (pinfunction "1_1") (pintype "passive"))
      (node (ref "CA3") (pin "2") (pinfunction "2_2") (pintype "passive"))
      (node (ref "CA3") (pin "3") (pinfunction "3_3") (pintype "passive"))
      (node (ref "CA3") (pin "4") (pinfunction "4_4") (pintype "passive"))
      (node (ref "CA4") (pin "1") (pinfunction "1_1") (pintype "passive"))
      (node (ref "CA4") (pin "2") (pinfunction "2_2") (pintype "passive"))
      (node (ref "CA4") (pin "3") (pinfunction "3_3") (pintype "passive"))
      (node (ref "CA4") (pin "4") (pinfunction "4_4") (pintype "passive"))
      (node (ref "CA5") (pin "1") (pinfunction "1_1") (pintype "passive"))
      (node (ref "CA5") (pin "2") (pinfunction "2_2") (pintype "passive"))
      (node (ref "CA5") (pin "3") (pinfunction "3_3") (pintype "passive"))
      (node (ref "CA5") (pin "4") (pinfunction "4_4") (pintype "passive"))
      (node (ref "CA6") (pin "1") (pinfunction "1_1") (pintype "passive"))
      (node (ref "CA6") (pin "2") (pinfunction "2_2") (pintype "passive"))
      (node (ref "CA6") (pin "3") (pinfunction "3_3") (pintype "passive"))
      (node (ref "CA6") (pin "4") (pinfunction "4_4") (pintype "passive"))
      (node (ref "CA6") (pin "7") (pinfunction "7_7") (pintype "passive"))
      (node (ref "CA7") (pin "1") (pinfunction "1_1") (pintype "passive"))
      (node (ref "CA7") (pin "2") (pinfunction "2_2") (pintype "passive"))
      (node (ref "CA7") (pin "3") (pinfunction "3_3") (pintype "passive"))
      (node (ref "CA7") (pin "4") (pinfunction "4_4") (pintype "passive"))
      (node (ref "CA8") (pin "1") (pinfunction "1_1") (pintype "passive"))
      (node (ref "CA8") (pin "2") (pinfunction "2_2") (pintype "passive"))
      (node (ref "CA8") (pin "3") (pinfunction "3_3") (pintype "passive"))
      (node (ref "CA8") (pin "4") (pinfunction "4_4") (pintype "passive"))
      (node (ref "CA9") (pin "1") (pinfunction "1_1") (pintype "passive"))
      (node (ref "CA9") (pin "2") (pinfunction "2_2") (pintype "passive"))
      (node (ref "CA9") (pin "3") (pinfunction "3_3") (pintype "passive"))
      (node (ref "CA9") (pin "4") (pinfunction "4_4") (pintype "passive"))
      (node (ref "D1") (pin "C") (pinfunction "C_C") (pintype "passive"))
      (node (ref "D2") (pin "C") (pinfunction "C_C") (pintype "passive"))
      (node (ref "D3") (pin "C") (pinfunction "C_C") (pintype "passive"))
      (node (ref "D4") (pin "C") (pinfunction "C_C") (pintype "passive"))
      (node (ref "D5") (pin "C") (pinfunction "C_C") (pintype "passive"))
      (node (ref "D6") (pin "C") (pinfunction "C_C") (pintype "passive"))
      (node (ref "D7") (pin "C") (pinfunction "C_C") (pintype "passive"))
      (node (ref "J1") (pin "11") (pinfunction "11_11") (pintype "passive"))
      (node (ref "J1") (pin "12") (pinfunction "12_12") (pintype "passive"))
      (node (ref "J1") (pin "6") (pinfunction "6_6") (pintype "passive"))
      (node (ref "J3") (pin "P$1") (pinfunction "1_P$1") (pintype "passive"))
      (node (ref "J4") (pin "GND") (pinfunction "GND_GND") (pintype "bidirectional"))
      (node (ref "J4") (pin "GNDBREAK") (pinfunction "GNDBREAK_GNDBREAK") (pintype "bidirectional"))
      (node (ref "JP1") (pin "1") (pinfunction "1_1") (pintype "passive"))
      (node (ref "JP3") (pin "1") (pinfunction "1_1") (pintype "passive"))
      (node (ref "JP4") (pin "1") (pinfunction "1_1") (pintype "passive"))
      (node (ref "JP5") (pin "1") (pinfunction "1_1") (pintype "passive"))
      (node (ref "JP7") (pin "3") (pinfunction "3_3") (pintype "passive"))
      (node (ref "R20") (pin "2") (pinfunction "2_2") (pintype "passive"))
      (node (ref "R21") (pin "1") (pinfunction "1_1") (pintype "passive"))
      (node (ref "R24") (pin "2") (pinfunction "2_2") (pintype "passive"))
      (node (ref "R25") (pin "2") (pinfunction "2_2") (pintype "passive"))
      (node (ref "R26") (pin "2") (pinfunction "2_2") (pintype "passive"))
      (node (ref "R27") (pin "1") (pinfunction "1_1") (pintype "passive"))
      (node (ref "R28") (pin "2") (pinfunction "2_2") (pintype "passive"))
      (node (ref "R29") (pin "2") (pinfunction "2_2") (pintype "passive"))
      (node (ref "R3") (pin "2") (pinfunction "2_2") (pintype "passive"))
      (node (ref "R6") (pin "2") (pinfunction "2_2") (pintype "passive"))
      (node (ref "R7") (pin "2") (pinfunction "2_2") (pintype "passive"))
      (node (ref "RA1") (pin "2") (pinfunction "2_2") (pintype "passive"))
      (node (ref "RA1") (pin "7") (pinfunction "7_7") (pintype "passive"))
      (node (ref "RA5") (pin "2") (pinfunction "2_2") (pintype "passive"))
      (node (ref "RA5") (pin "7") (pinfunction "7_7") (pintype "passive"))
      (node (ref "U1") (pin "20") (pinfunction "AVSS_2_20") (pintype "power_in"))
      (node (ref "U1") (pin "23") (pinfunction "AVSS_3_23") (pintype "power_in"))
      (node (ref "U1") (pin "25") (pinfunction "VREFN_25") (pintype "input"))
      (node (ref "U1") (pin "31") (pinfunction "RESV1_31") (pintype "input"))
      (node (ref "U1") (pin "32") (pinfunction "AVSS_4_32") (pintype "power_in"))
      (node (ref "U1") (pin "33") (pinfunction "DGND_2_33") (pintype "power_in"))
      (node (ref "U1") (pin "41") (pinfunction "DAISY_IN_41") (pintype "input"))
      (node (ref "U1") (pin "49") (pinfunction "DGND_3_49") (pintype "power_in"))
      (node (ref "U1") (pin "51") (pinfunction "DGND_51") (pintype "power_in"))
      (node (ref "U1") (pin "53") (pinfunction "AVSS1_53") (pintype "power_in"))
      (node (ref "U1") (pin "57") (pinfunction "AVSS_5_57") (pintype "power_in"))
      (node (ref "U1") (pin "58") (pinfunction "AVSS_58") (pintype "power_in"))
      (node (ref "U1") (pin "64") (pinfunction "RESERVED_64") (pintype "output"))
      (node (ref "U10") (pin "3") (pinfunction "GND_3") (pintype "power_in"))
      (node (ref "U11") (pin "1") (pinfunction "IO1_1") (pintype "bidirectional"))
      (node (ref "U11") (pin "3") (pinfunction "GND_3") (pintype "power_in"))
      (node (ref "U12") (pin "3") (pinfunction "GND_3") (pintype "power_in"))
      (node (ref "U13") (pin "3") (pinfunction "GND_3") (pintype "power_in"))
      (node (ref "U14") (pin "3") (pinfunction "GND_3") (pintype "power_in"))
      (node (ref "U15") (pin "3") (pinfunction "GND_3") (pintype "power_in"))
      (node (ref "U16") (pin "3") (pinfunction "GND_3") (pintype "power_in"))
      (node (ref "U17") (pin "1") (pinfunction "IO1_1") (pintype "bidirectional"))
      (node (ref "U17") (pin "3") (pinfunction "GND_3") (pintype "power_in"))
      (node (ref "U2") (pin "20") (pinfunction "AVSS_2_20") (pintype "power_in"))
      (node (ref "U2") (pin "23") (pinfunction "AVSS_3_23") (pintype "power_in"))
      (node (ref "U2") (pin "25") (pinfunction "VREFN_25") (pintype "input"))
      (node (ref "U2") (pin "31") (pinfunction "RESV1_31") (pintype "input"))
      (node (ref "U2") (pin "32") (pinfunction "AVSS_4_32") (pintype "power_in"))
      (node (ref "U2") (pin "33") (pinfunction "DGND_2_33") (pintype "power_in"))
      (node (ref "U2") (pin "41") (pinfunction "DAISY_IN_41") (pintype "input"))
      (node (ref "U2") (pin "49") (pinfunction "DGND_3_49") (pintype "power_in"))
      (node (ref "U2") (pin "51") (pinfunction "DGND_51") (pintype "power_in"))
      (node (ref "U2") (pin "53") (pinfunction "AVSS1_53") (pintype "power_in"))
      (node (ref "U2") (pin "57") (pinfunction "AVSS_5_57") (pintype "power_in"))
      (node (ref "U2") (pin "58") (pinfunction "AVSS_58") (pintype "power_in"))
      (node (ref "U2") (pin "64") (pinfunction "RESERVED_64") (pintype "output"))
      (node (ref "U3") (pin "11") (pinfunction "PGND2_11") (pintype "passive"))
      (node (ref "U3") (pin "3") (pinfunction "AGND_3") (pintype "passive"))
      (node (ref "U3") (pin "6") (pinfunction "MODE/SYNC_6") (pintype "passive"))
      (node (ref "U3") (pin "9") (pinfunction "PGND1_9") (pintype "passive"))
      (node (ref "U5") (pin "2") (pinfunction "GND_2") (pintype "passive"))
      (node (ref "U6") (pin "3") (pinfunction "GND_3") (pintype "power_in"))
      (node (ref "U7") (pin "3") (pinfunction "GND_3") (pintype "power_in"))
      (node (ref "U8") (pin "3") (pinfunction "GND_3") (pintype "power_in"))
      (node (ref "U9") (pin "3") (pinfunction "GND_3") (pintype "power_in"))
    )
    (net (code "103") (name "MISO_ADS") (class "Default")
      (node (ref "A1") (pin "P$6") (pinfunction "P6_P$6") (pintype "passive"))
      (node (ref "JP3") (pin "6") (pinfunction "6_6") (pintype "passive"))
      (node (ref "U1") (pin "43") (pinfunction "DOUT_43") (pintype "output"))
      (node (ref "U2") (pin "43") (pinfunction "DOUT_43") (pintype "output"))
    )
    (net (code "104") (name "MISO_SD") (class "Default")
      (node (ref "A1") (pin "P$12") (pinfunction "P12_P$12") (pintype "passive"))
      (node (ref "J1") (pin "7") (pinfunction "7_7") (pintype "passive"))
      (node (ref "JP3") (pin "12") (pinfunction "12_12") (pintype "passive"))
    )
    (net (code "105") (name "MOSI_ADS") (class "Default")
      (node (ref "A1") (pin "P$5") (pinfunction "P5_P$5") (pintype "passive"))
      (node (ref "JP3") (pin "5") (pinfunction "5_5") (pintype "passive"))
      (node (ref "U1") (pin "34") (pinfunction "DIN_34") (pintype "input"))
      (node (ref "U2") (pin "34") (pinfunction "DIN_34") (pintype "input"))
    )
    (net (code "106") (name "MOSI_SD") (class "Default")
      (node (ref "A1") (pin "P$11") (pinfunction "P11_P$11") (pintype "passive"))
      (node (ref "J1") (pin "3") (pinfunction "3_3") (pintype "passive"))
      (node (ref "JP3") (pin "11") (pinfunction "11_11") (pintype "passive"))
    )
    (net (code "107") (name "Net-(C10-Pad1)") (class "Default")
      (node (ref "C10") (pin "1") (pinfunction "1_1") (pintype "passive"))
      (node (ref "R5") (pin "2") (pinfunction "2_2") (pintype "passive"))
    )
    (net (code "108") (name "Net-(D1-PadA)") (class "Default")
      (node (ref "D1") (pin "A") (pinfunction "A_A") (pintype "passive"))
      (node (ref "R8") (pin "2") (pinfunction "2_2") (pintype "passive"))
    )
    (net (code "109") (name "Net-(D2-PadA)") (class "Default")
      (node (ref "D2") (pin "A") (pinfunction "A_A") (pintype "passive"))
      (node (ref "R9") (pin "2") (pinfunction "2_2") (pintype "passive"))
    )
    (net (code "110") (name "Net-(D3-PadA)") (class "Default")
      (node (ref "D3") (pin "A") (pinfunction "A_A") (pintype "passive"))
      (node (ref "R10") (pin "2") (pinfunction "2_2") (pintype "passive"))
    )
    (net (code "111") (name "Net-(D4-PadA)") (class "Default")
      (node (ref "D4") (pin "A") (pinfunction "A_A") (pintype "passive"))
      (node (ref "R11") (pin "2") (pinfunction "2_2") (pintype "passive"))
    )
    (net (code "112") (name "Net-(D5-PadA)") (class "Default")
      (node (ref "D5") (pin "A") (pinfunction "A_A") (pintype "passive"))
      (node (ref "R16") (pin "2") (pinfunction "2_2") (pintype "passive"))
    )
    (net (code "113") (name "Net-(D6-PadA)") (class "Default")
      (node (ref "D6") (pin "A") (pinfunction "A_A") (pintype "passive"))
      (node (ref "R17") (pin "2") (pinfunction "2_2") (pintype "passive"))
    )
    (net (code "114") (name "Net-(D7-PadA)") (class "Default")
      (node (ref "D7") (pin "A") (pinfunction "A_A") (pintype "passive"))
      (node (ref "R15") (pin "2") (pinfunction "2_2") (pintype "passive"))
    )
    (net (code "115") (name "Net-(J2-1)") (class "Default")
      (node (ref "J2") (pin "P$1") (pinfunction "1_P$1") (pintype "passive"))
      (node (ref "SW1") (pin "2") (pinfunction "2_2") (pintype "passive"))
    )
    (net (code "116") (name "Net-(JP6-Pad1)") (class "Default")
      (node (ref "JP6") (pin "1") (pinfunction "1_1") (pintype "passive"))
      (node (ref "R18") (pin "1") (pinfunction "1_1") (pintype "passive"))
    )
    (net (code "117") (name "Net-(U1-BIASIN)") (class "Default")
      (node (ref "C25") (pin "2") (pinfunction "2_2") (pintype "passive"))
      (node (ref "R12") (pin "2") (pinfunction "2_2") (pintype "passive"))
      (node (ref "U1") (pin "62") (pinfunction "BIASIN_62") (pintype "input"))
      (node (ref "U1") (pin "63") (pinfunction "BIASOUT_63") (pintype "output"))
    )
    (net (code "118") (name "Net-(U1-BIASREF)") (class "Default")
      (node (ref "R29") (pin "1") (pinfunction "1_1") (pintype "passive"))
      (node (ref "U1") (pin "60") (pinfunction "BIASREF_60") (pintype "input"))
    )
    (net (code "119") (name "Net-(U1-CLKSEL)") (class "Default")
      (node (ref "R22") (pin "1") (pinfunction "1_1") (pintype "passive"))
      (node (ref "U1") (pin "52") (pinfunction "CLKSEL_52") (pintype "input"))
    )
    (net (code "120") (name "Net-(U1-GPIO1)") (class "Default")
      (node (ref "R21") (pin "2") (pinfunction "2_2") (pintype "passive"))
      (node (ref "U1") (pin "42") (pinfunction "GPIO1_42") (pintype "bidirectional"))
    )
    (net (code "121") (name "Net-(U1-GPIO2)") (class "Default")
      (node (ref "R6") (pin "1") (pinfunction "1_1") (pintype "passive"))
      (node (ref "U1") (pin "44") (pinfunction "GPIO2_44") (pintype "bidirectional"))
    )
    (net (code "122") (name "Net-(U1-GPIO3)") (class "Default")
      (node (ref "R7") (pin "1") (pinfunction "1_1") (pintype "passive"))
      (node (ref "U1") (pin "45") (pinfunction "GPIO3_45") (pintype "bidirectional"))
    )
    (net (code "123") (name "Net-(U1-GPIO4)") (class "Default")
      (node (ref "R20") (pin "1") (pinfunction "1_1") (pintype "passive"))
      (node (ref "U1") (pin "46") (pinfunction "GPIO4_46") (pintype "bidirectional"))
    )
    (net (code "124") (name "Net-(U1-VCAP1)") (class "Default")
      (node (ref "C22") (pin "1") (pinfunction "1_1") (pintype "passive"))
      (node (ref "U1") (pin "28") (pinfunction "VCAP1_28") (pintype "passive"))
    )
    (net (code "125") (name "Net-(U1-VCAP2)") (class "Default")
      (node (ref "C21") (pin "1") (pinfunction "1_1") (pintype "passive"))
      (node (ref "U1") (pin "30") (pinfunction "VCAP2_30") (pintype "passive"))
    )
    (net (code "126") (name "Net-(U1-VCAP3)") (class "Default")
      (node (ref "C18") (pin "1") (pinfunction "1_1") (pintype "passive"))
      (node (ref "C19") (pin "1") (pinfunction "1_1") (pintype "passive"))
      (node (ref "U1") (pin "55") (pinfunction "VCAP3_55") (pintype "passive"))
    )
    (net (code "127") (name "Net-(U1-VCAP4)") (class "Default")
      (node (ref "C20") (pin "1") (pinfunction "1_1") (pintype "passive"))
      (node (ref "U1") (pin "26") (pinfunction "VCAP4_26") (pintype "output"))
    )
    (net (code "128") (name "Net-(U2-BIASIN)") (class "Default")
      (node (ref "C37") (pin "2") (pinfunction "2_2") (pintype "passive"))
      (node (ref "R13") (pin "2") (pinfunction "2_2") (pintype "passive"))
      (node (ref "U2") (pin "62") (pinfunction "BIASIN_62") (pintype "input"))
      (node (ref "U2") (pin "63") (pinfunction "BIASOUT_63") (pintype "output"))
    )
    (net (code "129") (name "Net-(U2-BIASREF)") (class "Default")
      (node (ref "R28") (pin "1") (pinfunction "1_1") (pintype "passive"))
      (node (ref "U2") (pin "60") (pinfunction "BIASREF_60") (pintype "input"))
    )
    (net (code "130") (name "Net-(U2-CLK)") (class "Default")
      (node (ref "R19") (pin "1") (pinfunction "1_1") (pintype "passive"))
      (node (ref "U2") (pin "37") (pinfunction "CLK_37") (pintype "input"))
    )
    (net (code "131") (name "Net-(U2-CLKSEL)") (class "Default")
      (node (ref "R23") (pin "1") (pinfunction "1_1") (pintype "passive"))
      (node (ref "U2") (pin "52") (pinfunction "CLKSEL_52") (pintype "input"))
    )
    (net (code "132") (name "Net-(U2-GPIO1)") (class "Default")
      (node (ref "R27") (pin "2") (pinfunction "2_2") (pintype "passive"))
      (node (ref "U2") (pin "42") (pinfunction "GPIO1_42") (pintype "bidirectional"))
    )
    (net (code "133") (name "Net-(U2-GPIO2)") (class "Default")
      (node (ref "R25") (pin "1") (pinfunction "1_1") (pintype "passive"))
      (node (ref "U2") (pin "44") (pinfunction "GPIO2_44") (pintype "bidirectional"))
    )
    (net (code "134") (name "Net-(U2-GPIO3)") (class "Default")
      (node (ref "R24") (pin "1") (pinfunction "1_1") (pintype "passive"))
      (node (ref "U2") (pin "45") (pinfunction "GPIO3_45") (pintype "bidirectional"))
    )
    (net (code "135") (name "Net-(U2-GPIO4)") (class "Default")
      (node (ref "R26") (pin "1") (pinfunction "1_1") (pintype "passive"))
      (node (ref "U2") (pin "46") (pinfunction "GPIO4_46") (pintype "bidirectional"))
    )
    (net (code "136") (name "Net-(U2-VCAP1)") (class "Default")
      (node (ref "C34") (pin "1") (pinfunction "1_1") (pintype "passive"))
      (node (ref "U2") (pin "28") (pinfunction "VCAP1_28") (pintype "passive"))
    )
    (net (code "137") (name "Net-(U2-VCAP2)") (class "Default")
      (node (ref "C33") (pin "1") (pinfunction "1_1") (pintype "passive"))
      (node (ref "U2") (pin "30") (pinfunction "VCAP2_30") (pintype "passive"))
    )
    (net (code "138") (name "Net-(U2-VCAP3)") (class "Default")
      (node (ref "C30") (pin "1") (pinfunction "1_1") (pintype "passive"))
      (node (ref "C31") (pin "1") (pinfunction "1_1") (pintype "passive"))
      (node (ref "U2") (pin "55") (pinfunction "VCAP3_55") (pintype "passive"))
    )
    (net (code "139") (name "Net-(U2-VCAP4)") (class "Default")
      (node (ref "C32") (pin "1") (pinfunction "1_1") (pintype "passive"))
      (node (ref "U2") (pin "26") (pinfunction "VCAP4_26") (pintype "output"))
    )
    (net (code "140") (name "Net-(U3-CBOOT)") (class "Default")
      (node (ref "C8") (pin "2") (pinfunction "2_2") (pintype "passive"))
      (node (ref "R2") (pin "1") (pinfunction "1_1") (pintype "passive"))
      (node (ref "U3") (pin "14") (pinfunction "CBOOT_14") (pintype "passive"))
    )
    (net (code "141") (name "Net-(U3-EN)") (class "Default")
      (node (ref "R1") (pin "1") (pinfunction "1_1") (pintype "passive"))
      (node (ref "U3") (pin "7") (pinfunction "EN_7") (pintype "passive"))
    )
    (net (code "142") (name "Net-(U3-FB)") (class "Default")
      (node (ref "C10") (pin "2") (pinfunction "2_2") (pintype "passive"))
      (node (ref "R3") (pin "1") (pinfunction "1_1") (pintype "passive"))
      (node (ref "R4") (pin "2") (pinfunction "2_2") (pintype "passive"))
      (node (ref "U3") (pin "4") (pinfunction "FB_4") (pintype "passive"))
    )
    (net (code "143") (name "Net-(U3-RBOOT)") (class "Default")
      (node (ref "R2") (pin "2") (pinfunction "2_2") (pintype "passive"))
      (node (ref "U3") (pin "13") (pinfunction "RBOOT_13") (pintype "passive"))
    )
    (net (code "144") (name "Net-(U3-SW)") (class "Default")
      (node (ref "C8") (pin "1") (pinfunction "1_1") (pintype "passive"))
      (node (ref "L1") (pin "1") (pinfunction "1_1") (pintype "passive"))
      (node (ref "U3") (pin "10") (pinfunction "SW_10") (pintype "passive"))
    )
    (net (code "145") (name "Net-(U3-VCC)") (class "Default")
      (node (ref "C9") (pin "1") (pinfunction "1_1") (pintype "passive"))
      (node (ref "U3") (pin "2") (pinfunction "VCC_2") (pintype "power_in"))
    )
    (net (code "146") (name "Net-(U5-BYPASS)") (class "Default")
      (node (ref "C12") (pin "1") (pinfunction "1_1") (pintype "passive"))
      (node (ref "U5") (pin "4") (pinfunction "BYPASS_4") (pintype "passive"))
    )
    (net (code "147") (name "SCK_SD") (class "Default")
      (node (ref "A1") (pin "P$13") (pinfunction "P13_P$13") (pintype "passive"))
      (node (ref "J1") (pin "5") (pinfunction "5_5") (pintype "passive"))
      (node (ref "JP3") (pin "13") (pinfunction "13_13") (pintype "passive"))
    )
    (net (code "148") (name "SCLK_ADS") (class "Default")
      (node (ref "A1") (pin "P$7") (pinfunction "P7_P$7") (pintype "passive"))
      (node (ref "JP3") (pin "7") (pinfunction "7_7") (pintype "passive"))
      (node (ref "U1") (pin "40") (pinfunction "SCLK_40") (pintype "input"))
      (node (ref "U2") (pin "40") (pinfunction "SCLK_40") (pintype "input"))
    )
    (net (code "149") (name "SCL_IMU") (class "Default")
      (node (ref "A1") (pin "P$27") (pinfunction "P27_P$27") (pintype "passive"))
      (node (ref "JP1") (pin "4") (pinfunction "4_4") (pintype "passive"))
      (node (ref "JP2") (pin "7") (pinfunction "7_7") (pintype "passive"))
    )
    (net (code "150") (name "SDA_IMU") (class "Default")
      (node (ref "A1") (pin "P$28") (pinfunction "P28_P$28") (pintype "passive"))
      (node (ref "JP1") (pin "3") (pinfunction "3_3") (pintype "passive"))
      (node (ref "JP2") (pin "8") (pinfunction "8_8") (pintype "passive"))
    )
    (net (code "151") (name "SRB1") (class "Default")
      (node (ref "CA5") (pin "5") (pinfunction "5_5") (pintype "passive"))
      (node (ref "R45") (pin "5") (pinfunction "5_5") (pintype "passive"))
      (node (ref "U1") (pin "17") (pinfunction "SRB1_17") (pintype "bidirectional"))
    )
    (net (code "152") (name "SRB1_1") (class "Default")
      (node (ref "CA10") (pin "5") (pinfunction "5_5") (pintype "passive"))
      (node (ref "R14") (pin "5") (pinfunction "5_5") (pintype "passive"))
      (node (ref "U2") (pin "17") (pinfunction "SRB1_17") (pintype "bidirectional"))
    )
    (net (code "153") (name "SRB1_OUT") (class "Default")
      (node (ref "J22") (pin "PWR") (pinfunction "PWR_PWR") (pintype "bidirectional"))
      (node (ref "R45") (pin "4") (pinfunction "4_4") (pintype "passive"))
      (node (ref "U10") (pin "5") (pinfunction "IO4_5") (pintype "bidirectional"))
    )
    (net (code "154") (name "SRB1_OUT_1") (class "Default")
      (node (ref "J24") (pin "PWR") (pinfunction "PWR_PWR") (pintype "bidirectional"))
      (node (ref "R14") (pin "4") (pinfunction "4_4") (pintype "passive"))
      (node (ref "U16") (pin "5") (pinfunction "IO4_5") (pintype "bidirectional"))
    )
    (net (code "155") (name "SRB2") (class "Default")
      (node (ref "CA5") (pin "6") (pinfunction "6_6") (pintype "passive"))
      (node (ref "R45") (pin "6") (pinfunction "6_6") (pintype "passive"))
      (node (ref "U1") (pin "18") (pinfunction "SRB2_18") (pintype "bidirectional"))
    )
    (net (code "156") (name "SRB2_1") (class "Default")
      (node (ref "CA10") (pin "6") (pinfunction "6_6") (pintype "passive"))
      (node (ref "R14") (pin "6") (pinfunction "6_6") (pintype "passive"))
      (node (ref "U2") (pin "18") (pinfunction "SRB2_18") (pintype "bidirectional"))
    )
    (net (code "157") (name "SRB2_OUT") (class "Default")
      (node (ref "J22") (pin "GND") (pinfunction "GND_GND") (pintype "bidirectional"))
      (node (ref "J22") (pin "GNDBREAK") (pinfunction "GNDBREAK_GNDBREAK") (pintype "bidirectional"))
      (node (ref "R45") (pin "3") (pinfunction "3_3") (pintype "passive"))
      (node (ref "U10") (pin "2") (pinfunction "IO2_2") (pintype "bidirectional"))
    )
    (net (code "158") (name "SRB2_OUT_1") (class "Default")
      (node (ref "J24") (pin "GND") (pinfunction "GND_GND") (pintype "bidirectional"))
      (node (ref "J24") (pin "GNDBREAK") (pinfunction "GNDBREAK_GNDBREAK") (pintype "bidirectional"))
      (node (ref "R14") (pin "3") (pinfunction "3_3") (pintype "passive"))
      (node (ref "U16") (pin "2") (pinfunction "IO2_2") (pintype "bidirectional"))
    )
    (net (code "159") (name "START_ADS") (class "Default")
      (node (ref "A1") (pin "P$16") (pinfunction "P16_P$16") (pintype "passive"))
      (node (ref "JP3") (pin "16") (pinfunction "16_16") (pintype "passive"))
      (node (ref "U1") (pin "38") (pinfunction "START_38") (pintype "input"))
      (node (ref "U2") (pin "38") (pinfunction "START_38") (pintype "input"))
    )
    (net (code "160") (name "VREFP") (class "Default")
      (node (ref "C23") (pin "1") (pinfunction "1_1") (pintype "passive"))
      (node (ref "C24") (pin "1") (pinfunction "1_1") (pintype "passive"))
      (node (ref "JP8") (pin "1") (pinfunction "1_1") (pintype "passive"))
      (node (ref "U1") (pin "24") (pinfunction "VREFP_24") (pintype "bidirectional"))
    )
    (net (code "161") (name "VREFP_1") (class "Default")
      (node (ref "C35") (pin "1") (pinfunction "1_1") (pintype "passive"))
      (node (ref "C36") (pin "1") (pinfunction "1_1") (pintype "passive"))
      (node (ref "JP9") (pin "1") (pinfunction "1_1") (pintype "passive"))
      (node (ref "U2") (pin "24") (pinfunction "VREFP_24") (pintype "bidirectional"))
    )
    (net (code "162") (name "unconnected-(J1-Pad1)") (class "Default")
      (node (ref "J1") (pin "1") (pinfunction "1_1") (pintype "no_connect"))
    )
    (net (code "163") (name "unconnected-(J1-Pad8)") (class "Default")
      (node (ref "J1") (pin "8") (pinfunction "8_8") (pintype "no_connect"))
    )
    (net (code "164") (name "unconnected-(J1-Pad9)") (class "Default")
      (node (ref "J1") (pin "9") (pinfunction "9_9") (pintype "no_connect"))
    )
    (net (code "165") (name "unconnected-(J1-Pad10)") (class "Default")
      (node (ref "J1") (pin "10") (pinfunction "10_10") (pintype "no_connect"))
    )
    (net (code "166") (name "unconnected-(SW2-Pad2)") (class "Default")
      (node (ref "SW2") (pin "2") (pinfunction "2_2") (pintype "passive"))
    )
    (net (code "167") (name "unconnected-(U1-NC-Pad29)") (class "Default")
      (node (ref "U1") (pin "29") (pinfunction "NC_29") (pintype "no_connect"))
    )
    (net (code "168") (name "unconnected-(U1-NC_2-Pad27)") (class "Default")
      (node (ref "U1") (pin "27") (pinfunction "NC_2_27") (pintype "no_connect"))
    )
    (net (code "169") (name "unconnected-(U2-NC-Pad29)") (class "Default")
      (node (ref "U2") (pin "29") (pinfunction "NC_29") (pintype "no_connect"))
    )
    (net (code "170") (name "unconnected-(U2-NC_2-Pad27)") (class "Default")
      (node (ref "U2") (pin "27") (pinfunction "NC_2_27") (pintype "no_connect"))
    )
    (net (code "171") (name "unconnected-(U2-~{DRDY}-Pad47)") (class "Default")
      (node (ref "U2") (pin "47") (pinfunction "~{DRDY}_47") (pintype "output"))
    )
    (net (code "172") (name "unconnected-(U3-PGOOD-Pad5)") (class "Default")
      (node (ref "U3") (pin "5") (pinfunction "PGOOD_5") (pintype "no_connect"))
    )
    (net (code "173") (name "unconnected-(U6-IO1-Pad1)") (class "Default")
      (node (ref "U6") (pin "1") (pinfunction "IO1_1") (pintype "bidirectional"))
    )
    (net (code "174") (name "unconnected-(U6-NC-Pad6)") (class "Default")
      (node (ref "U6") (pin "6") (pinfunction "NC_6") (pintype "no_connect"))
    )
    (net (code "175") (name "unconnected-(U7-NC-Pad6)") (class "Default")
      (node (ref "U7") (pin "6") (pinfunction "NC_6") (pintype "no_connect"))
    )
    (net (code "176") (name "unconnected-(U8-NC-Pad6)") (class "Default")
      (node (ref "U8") (pin "6") (pinfunction "NC_6") (pintype "no_connect"))
    )
    (net (code "177") (name "unconnected-(U9-NC-Pad6)") (class "Default")
      (node (ref "U9") (pin "6") (pinfunction "NC_6") (pintype "no_connect"))
    )
    (net (code "178") (name "unconnected-(U10-IO3-Pad4)") (class "Default")
      (node (ref "U10") (pin "4") (pinfunction "IO3_4") (pintype "bidirectional"))
    )
    (net (code "179") (name "unconnected-(U10-NC-Pad6)") (class "Default")
      (node (ref "U10") (pin "6") (pinfunction "NC_6") (pintype "no_connect"))
    )
    (net (code "180") (name "unconnected-(U11-IO4-Pad5)") (class "Default")
      (node (ref "U11") (pin "5") (pinfunction "IO4_5") (pintype "bidirectional"))
    )
    (net (code "181") (name "unconnected-(U11-NC-Pad6)") (class "Default")
      (node (ref "U11") (pin "6") (pinfunction "NC_6") (pintype "no_connect"))
    )
    (net (code "182") (name "unconnected-(U12-IO1-Pad1)") (class "Default")
      (node (ref "U12") (pin "1") (pinfunction "IO1_1") (pintype "bidirectional"))
    )
    (net (code "183") (name "unconnected-(U12-NC-Pad6)") (class "Default")
      (node (ref "U12") (pin "6") (pinfunction "NC_6") (pintype "no_connect"))
    )
    (net (code "184") (name "unconnected-(U13-NC-Pad6)") (class "Default")
      (node (ref "U13") (pin "6") (pinfunction "NC_6") (pintype "no_connect"))
    )
    (net (code "185") (name "unconnected-(U14-NC-Pad6)") (class "Default")
      (node (ref "U14") (pin "6") (pinfunction "NC_6") (pintype "no_connect"))
    )
    (net (code "186") (name "unconnected-(U15-NC-Pad6)") (class "Default")
      (node (ref "U15") (pin "6") (pinfunction "NC_6") (pintype "no_connect"))
    )
    (net (code "187") (name "unconnected-(U16-IO3-Pad4)") (class "Default")
      (node (ref "U16") (pin "4") (pinfunction "IO3_4") (pintype "bidirectional"))
    )
    (net (code "188") (name "unconnected-(U16-NC-Pad6)") (class "Default")
      (node (ref "U16") (pin "6") (pinfunction "NC_6") (pintype "no_connect"))
    )
    (net (code "189") (name "unconnected-(U17-IO4-Pad5)") (class "Default")
      (node (ref "U17") (pin "5") (pinfunction "IO4_5") (pintype "bidirectional"))
    )
    (net (code "190") (name "unconnected-(U17-NC-Pad6)") (class "Default")
      (node (ref "U17") (pin "6") (pinfunction "NC_6") (pintype "no_connect"))
    )
    (net (code "191") (name "~{CS}_ADS_0") (class "Default")
      (node (ref "A1") (pin "P$15") (pinfunction "P15_P$15") (pintype "passive"))
      (node (ref "JP3") (pin "15") (pinfunction "15_15") (pintype "passive"))
      (node (ref "R31") (pin "1") (pinfunction "1_1") (pintype "passive"))
      (node (ref "U1") (pin "39") (pinfunction "~{CS}_39") (pintype "input"))
    )
    (net (code "192") (name "~{CS}_ADS_1") (class "Default")
      (node (ref "A1") (pin "P$20") (pinfunction "P20_P$20") (pintype "passive"))
      (node (ref "JP3") (pin "20") (pinfunction "20_20") (pintype "passive"))
      (node (ref "R32") (pin "1") (pinfunction "1_1") (pintype "passive"))
      (node (ref "U2") (pin "39") (pinfunction "~{CS}_39") (pintype "input"))
    )
    (net (code "193") (name "~{CS}_SD") (class "Default")
      (node (ref "A1") (pin "P$14") (pinfunction "P14_P$14") (pintype "passive"))
      (node (ref "J1") (pin "2") (pinfunction "2_2") (pintype "passive"))
      (node (ref "JP3") (pin "14") (pinfunction "14_14") (pintype "passive"))
    )
    (net (code "194") (name "~{INT}_ADS") (class "Default")
      (node (ref "A1") (pin "P$8") (pinfunction "P8_P$8") (pintype "passive"))
      (node (ref "JP3") (pin "8") (pinfunction "8_8") (pintype "passive"))
      (node (ref "U1") (pin "47") (pinfunction "~{DRDY}_47") (pintype "output"))
    )
    (net (code "195") (name "~{RESET}_ADS_0") (class "Default")
      (node (ref "A1") (pin "P$19") (pinfunction "P19_P$19") (pintype "passive"))
      (node (ref "JP3") (pin "19") (pinfunction "19_19") (pintype "passive"))
      (node (ref "R30") (pin "1") (pinfunction "1_1") (pintype "passive"))
      (node (ref "U1") (pin "36") (pinfunction "~{RESET}_36") (pintype "input"))
    )
    (net (code "196") (name "~{RESET}_ADS_1") (class "Default")
      (node (ref "R33") (pin "1") (pinfunction "1_1") (pintype "passive"))
      (node (ref "U2") (pin "36") (pinfunction "~{RESET}_36") (pintype "input"))
    )
  )
)
